# Sheet1.net
KiCad netlist of a schematic drawn in Altium Designer
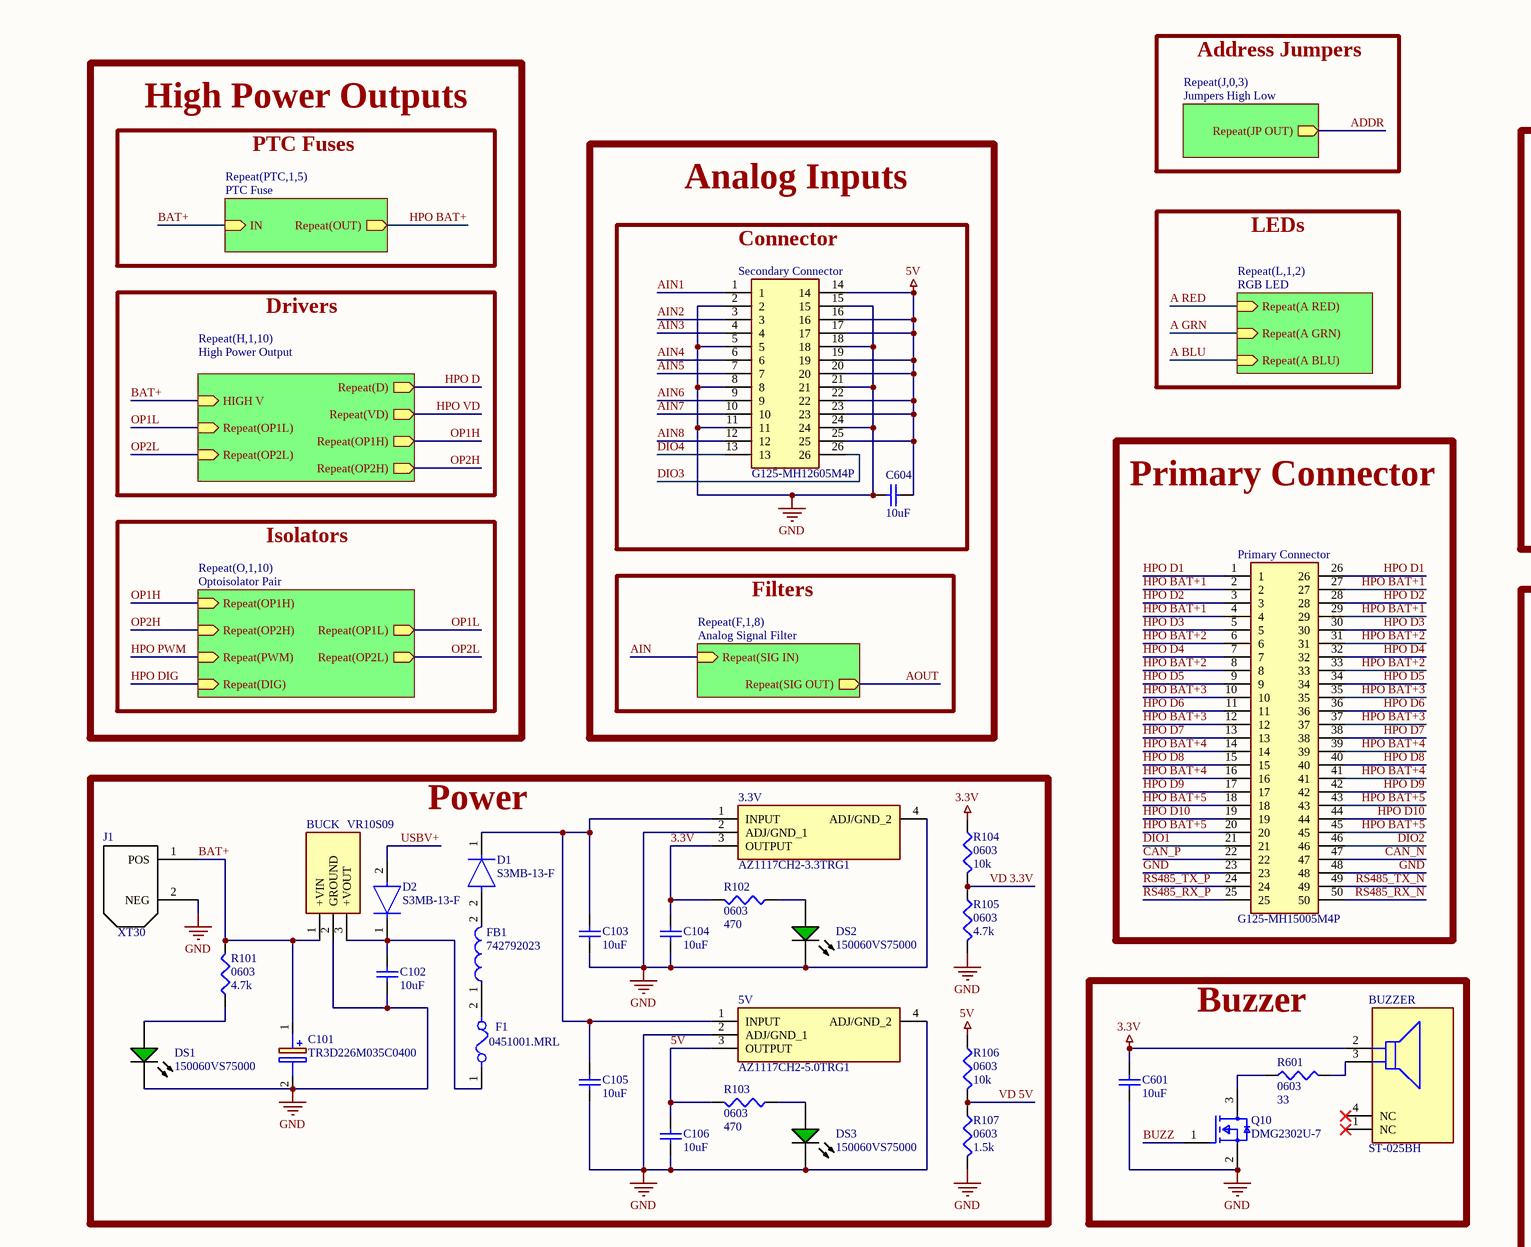
[diagram p0: Sheet1.SchDoc, top left]
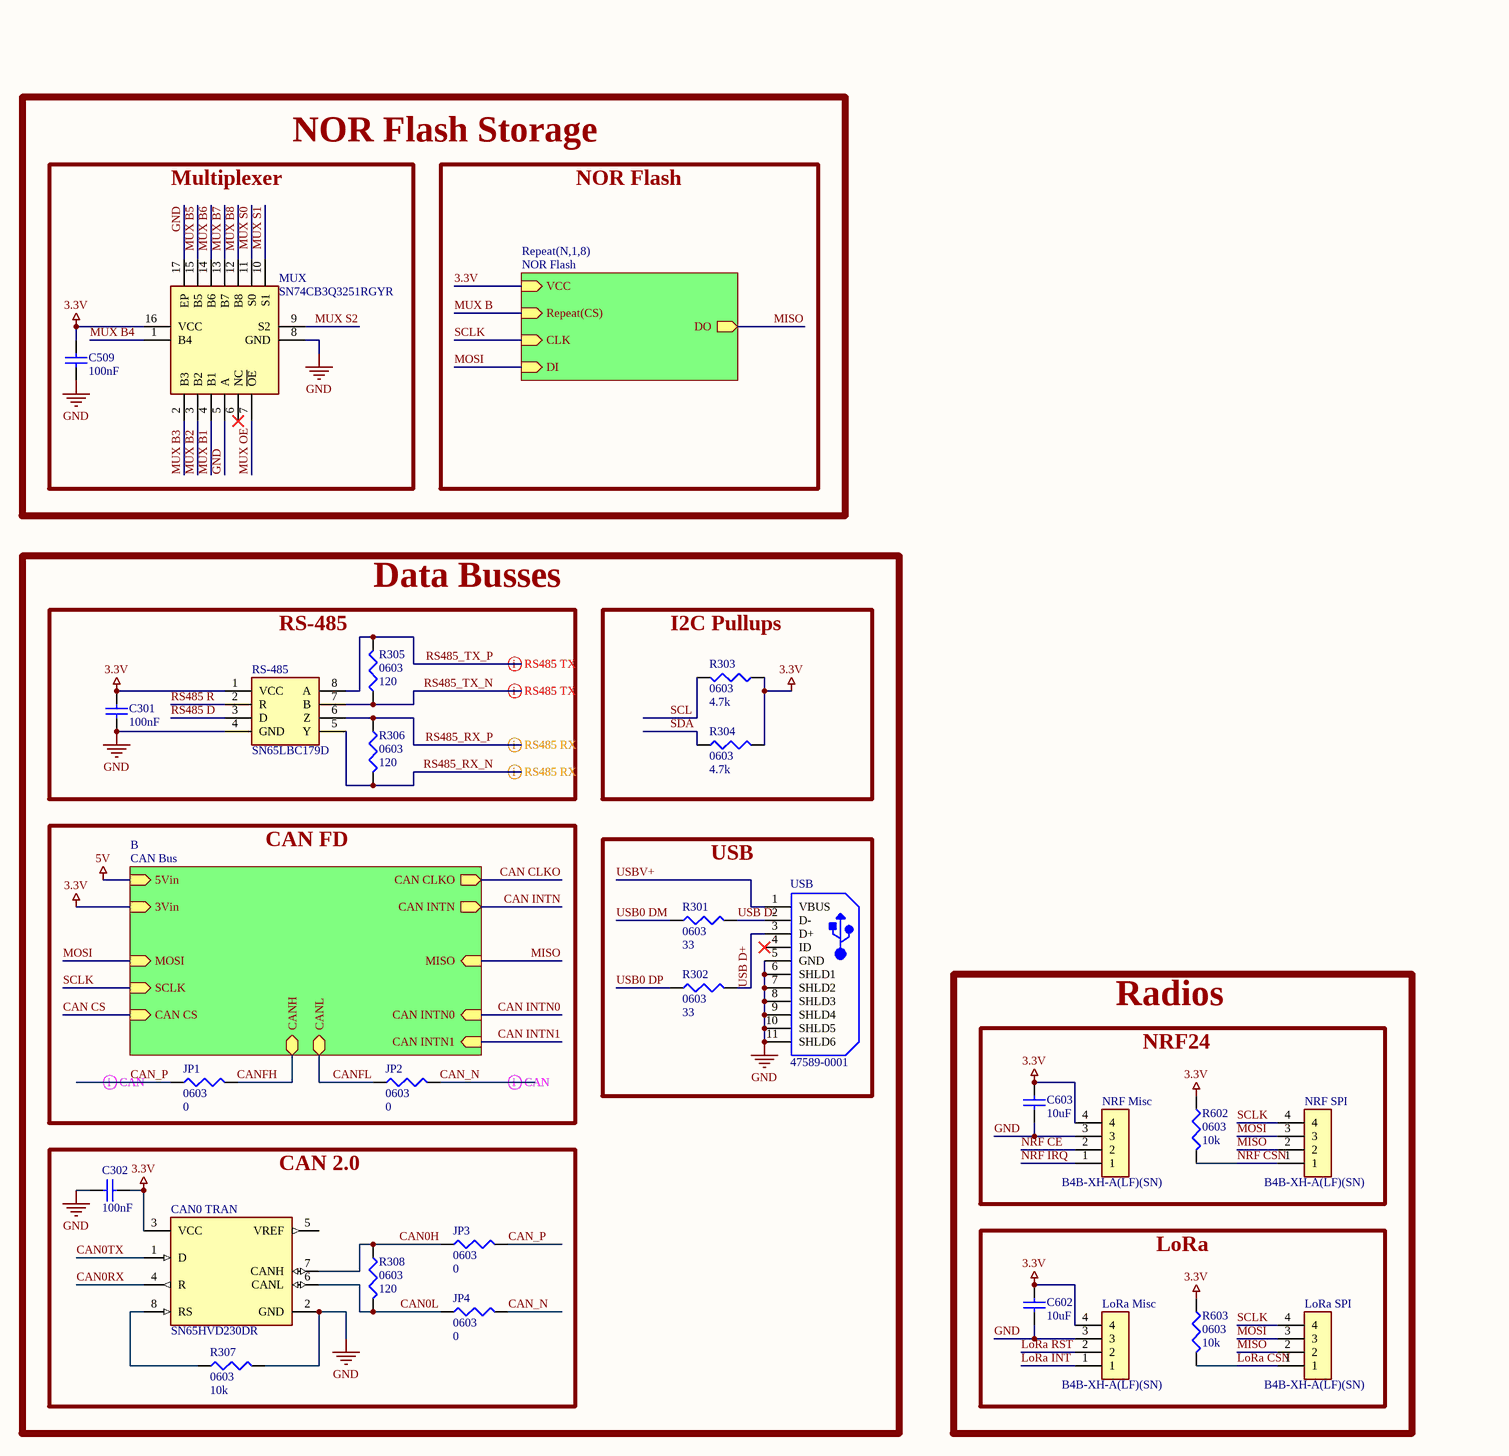
[diagram p1: Sheet1.SchDoc, top right]
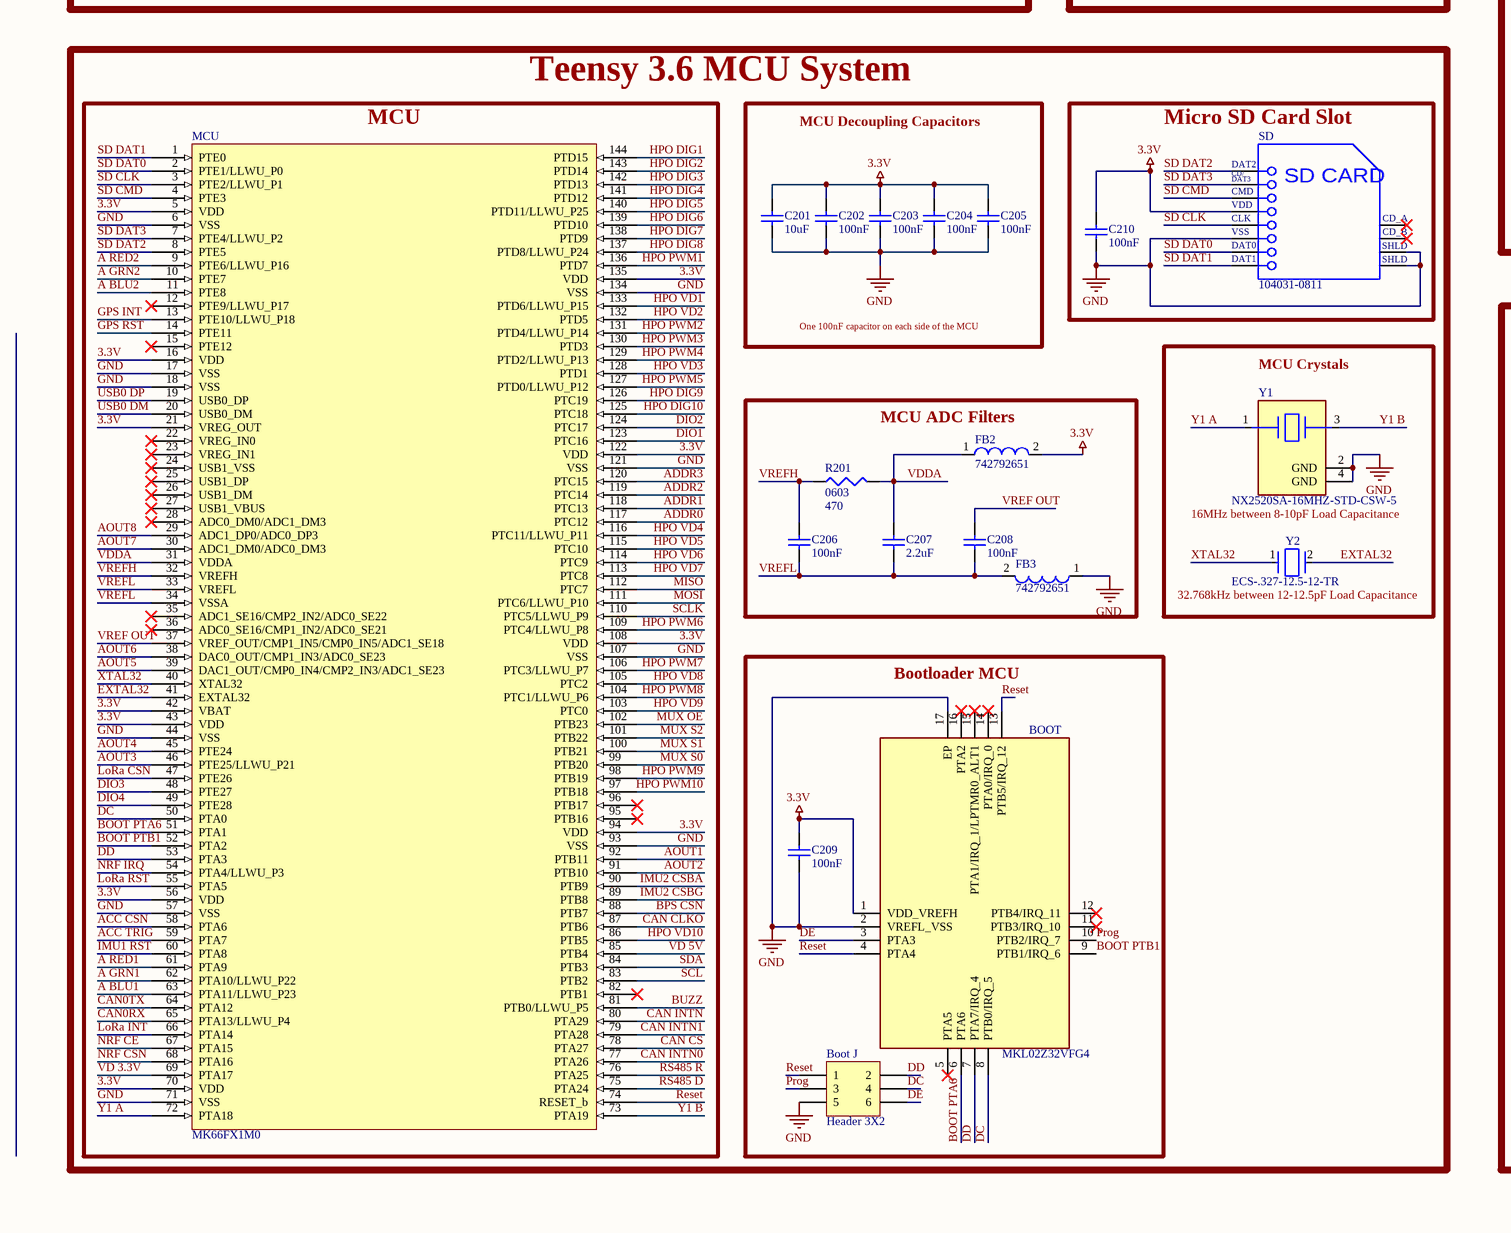
[diagram p2: Sheet1.SchDoc, bottom left]
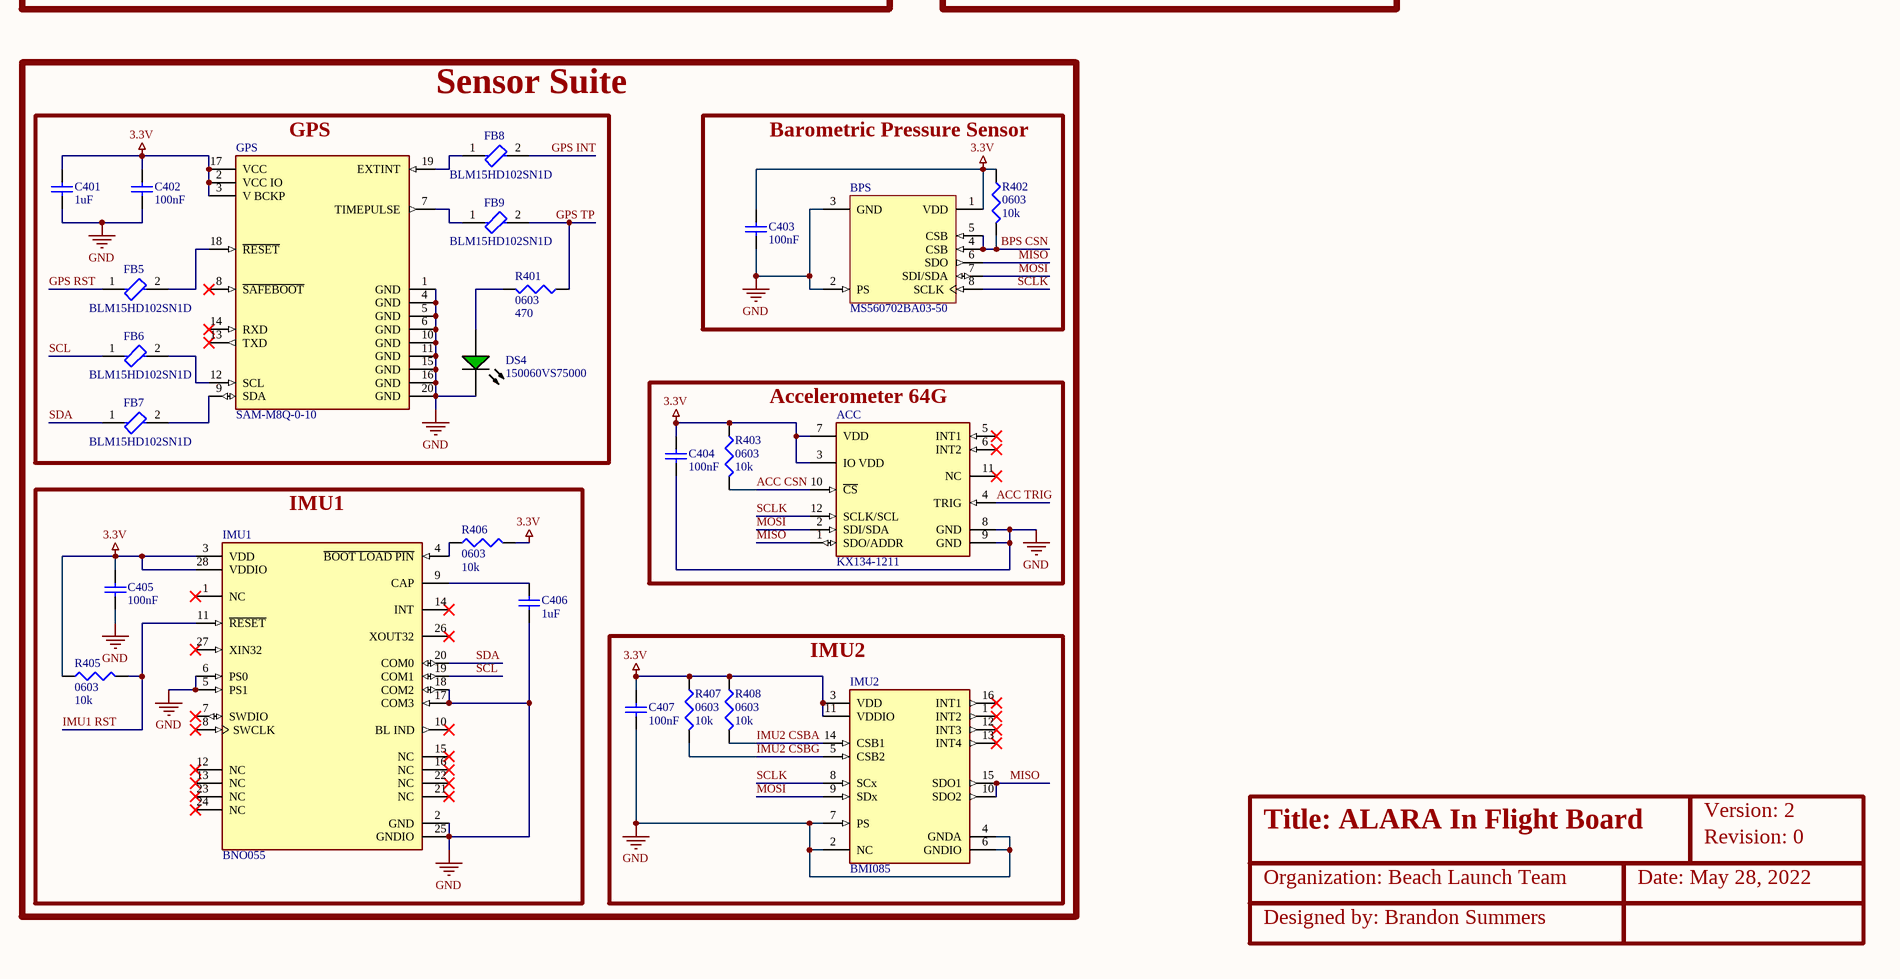
[diagram p3: Sheet1.SchDoc, bottom right]

(export (version "E")
  (design (tool "Eeschema 10.0.6"))
  (components
    (comp (ref "3.3V")
      (value "AZ1117CH2-3.3TRG1")
      (footprint "SamacSys:SOT230P700X180-4N")
      (description "Integrated Circuit")
      (libsource (lib "SamacSys") (part "AZ1117CH2-3.3TRG1"))
    )
    (comp (ref "5V")
      (value "AZ1117CH2-5.0TRG1")
      (footprint "SamacSys:SOT230P700X180-4N")
      (description "Integrated Circuit")
      (libsource (lib "SamacSys") (part "AZ1117CH2-5.0TRG1"))
    )
    (comp (ref "ACC")
      (value "KX134-1211")
      (footprint "FP-KX134-1211-MFG")
      (description "105C OPERATING HIGHER BANDWIDTH,")
      (libsource (lib "Altium Content Vault") (part "690d2a4d51cffb5fe50aad75ddab18e"))
    )
    (comp (ref "BOOT")
      (value "MKL02Z32VFG4")
      (footprint "SamacSys:QFN50P300X300X65-17N-D")
      (description "Integrated Circuit")
      (fields (field (name "MOUSER PART NUMBER") "841-MKL02Z32VFG4"))
      (libsource (lib "*") (part "MKL02Z32VFG4"))
    )
    (comp (ref "Boot J")
      (value "Header 3X2")
      (footprint "HDR2X3")
      (description "Header, 3-Pin, Dual row")
      (fields (field (name "PUBLISHER") "Altium Limited"))
      (libsource (lib "Miscellaneous Connectors") (part "Header 3X2"))
    )
    (comp (ref "BPS")
      (value "MS560702BA03-50")
      (footprint "TECO-MS560702BA03-50_V")
      (fields (field (name "MANUFACTURER") "TE Connectivity"))
      (libsource (lib "Altium Content Vault") (part "TECO-MS560702BA03-8"))
    )
    (comp (ref "BUCK")
      (value "VR10S09")
      (footprint "SamacSys:VR10S09")
      (description "Power Supply")
      (libsource (lib "SamacSys") (part "VR10S09"))
    )
    (comp (ref "BUZZER")
      (value "ST-025BH")
      (footprint "FP-ST-025BH-MFG")
      (description "AUDIO MAGNETIC XDCR 2-4V SMD")
      (fields
        (field (name "OCTOPART") "https://octopart.com/st-025bh-soberton-22171825")
        (field (name "MANUFACTURER") "Soberton Inc.")
      )
      (libsource (lib "Altium Content Vault") (part "31cc79d7b80ed2267c9b1676827f62c"))
    )
    (comp (ref "C101")
      (value "TR3D226M035C0400")
      (footprint "SamacSys:CAPPM7343X310N")
      (description "Capacitor Polarised")
      (libsource (lib "SamacSys") (part "TR3D226M035C0400"))
    )
    (comp (ref "C102")
      (value "10uF")
      (footprint "CAPC1608X95X40ML15T15")
      (fields (field (name "MANUFACTURER") "Vitramon") (field (name "PART NUMBER") "VJ0603Y104KXQCW1BC"))
      (libsource (lib "Altium Content Vault") (part "CAP"))
    )
    (comp (ref "C103")
      (value "10uF")
      (footprint "CAPC1608X95X40ML15T15")
      (fields (field (name "MANUFACTURER") "Vitramon") (field (name "PART NUMBER") "VJ0603Y104KXQCW1BC"))
      (libsource (lib "Altium Content Vault") (part "CAP"))
    )
    (comp (ref "C104")
      (value "10uF")
      (footprint "CAPC1608X95X40ML15T15")
      (fields (field (name "MANUFACTURER") "Vitramon") (field (name "PART NUMBER") "VJ0603Y104KXQCW1BC"))
      (libsource (lib "Altium Content Vault") (part "CAP"))
    )
    (comp (ref "C105")
      (value "10uF")
      (footprint "CAPC1608X95X40ML15T15")
      (fields (field (name "MANUFACTURER") "Vitramon") (field (name "PART NUMBER") "VJ0603Y104KXQCW1BC"))
      (libsource (lib "Altium Content Vault") (part "CAP"))
    )
    (comp (ref "C106")
      (value "10uF")
      (footprint "CAPC1608X95X40ML15T15")
      (fields (field (name "MANUFACTURER") "Vitramon") (field (name "PART NUMBER") "VJ0603Y104KXQCW1BC"))
      (libsource (lib "Altium Content Vault") (part "CAP"))
    )
    (comp (ref "C201")
      (value "10uF")
      (footprint "CAPC1608X95X40ML15T15")
      (fields (field (name "MANUFACTURER") "Vitramon") (field (name "PART NUMBER") "VJ0603Y104KXQCW1BC"))
      (libsource (lib "Altium Content Vault") (part "CAP"))
    )
    (comp (ref "C202")
      (value "100nF")
      (footprint "CAPC1608X95X40ML15T15")
      (fields (field (name "MANUFACTURER") "Vitramon") (field (name "PART NUMBER") "VJ0603Y104KXQCW1BC"))
      (libsource (lib "Altium Content Vault") (part "CAP"))
    )
    (comp (ref "C203")
      (value "100nF")
      (footprint "CAPC1608X95X40ML15T15")
      (fields (field (name "MANUFACTURER") "Vitramon") (field (name "PART NUMBER") "VJ0603Y104KXQCW1BC"))
      (libsource (lib "Altium Content Vault") (part "CAP"))
    )
    (comp (ref "C204")
      (value "100nF")
      (footprint "CAPC1608X95X40ML15T15")
      (fields (field (name "MANUFACTURER") "Vitramon") (field (name "PART NUMBER") "VJ0603Y104KXQCW1BC"))
      (libsource (lib "Altium Content Vault") (part "CAP"))
    )
    (comp (ref "C205")
      (value "100nF")
      (footprint "CAPC1608X95X40ML15T15")
      (fields (field (name "MANUFACTURER") "Vitramon") (field (name "PART NUMBER") "VJ0603Y104KXQCW1BC"))
      (libsource (lib "Altium Content Vault") (part "CAP"))
    )
    (comp (ref "C206")
      (value "100nF")
      (footprint "CAPC1608X95X40ML15T15")
      (fields (field (name "MANUFACTURER") "Vitramon") (field (name "PART NUMBER") "VJ0603Y104KXQCW1BC"))
      (libsource (lib "Altium Content Vault") (part "CAP"))
    )
    (comp (ref "C207")
      (value "2.2uF")
      (footprint "CAPC1608X95X40ML15T15")
      (fields (field (name "MANUFACTURER") "Vitramon") (field (name "PART NUMBER") "VJ0603Y104KXQCW1BC"))
      (libsource (lib "Altium Content Vault") (part "CAP"))
    )
    (comp (ref "C208")
      (value "100nF")
      (footprint "CAPC1608X95X40ML15T15")
      (fields (field (name "MANUFACTURER") "Vitramon") (field (name "PART NUMBER") "VJ0603Y104KXQCW1BC"))
      (libsource (lib "Altium Content Vault") (part "CAP"))
    )
    (comp (ref "C209")
      (value "100nF")
      (footprint "CAPC1608X95X40ML15T15")
      (fields (field (name "MANUFACTURER") "Vitramon") (field (name "PART NUMBER") "VJ0603Y104KXQCW1BC"))
      (libsource (lib "Altium Content Vault") (part "CAP"))
    )
    (comp (ref "C210")
      (value "100nF")
      (footprint "CAPC1608X95X40ML15T15")
      (fields (field (name "MANUFACTURER") "Vitramon") (field (name "PART NUMBER") "VJ0603Y104KXQCW1BC"))
      (libsource (lib "Altium Content Vault") (part "CAP"))
    )
    (comp (ref "C301")
      (value "100nF")
      (footprint "CAPC1608X95X40ML15T15")
      (fields (field (name "MANUFACTURER") "Vitramon") (field (name "PART NUMBER") "VJ0603Y104KXQCW1BC"))
      (libsource (lib "Altium Content Vault") (part "CAP"))
    )
    (comp (ref "C302")
      (value "100nF")
      (footprint "CAPC1608X95X40ML15T15")
      (fields (field (name "MANUFACTURER") "Vitramon") (field (name "PART NUMBER") "VJ0603Y104KXQCW1BC"))
      (libsource (lib "Altium Content Vault") (part "CAP"))
    )
    (comp (ref "C401")
      (value "1uF")
      (footprint "CAPC1608X95X40ML15T15")
      (fields (field (name "MANUFACTURER") "Vitramon") (field (name "PART NUMBER") "VJ0603Y104KXQCW1BC"))
      (libsource (lib "Altium Content Vault") (part "CAP"))
    )
    (comp (ref "C402")
      (value "100nF")
      (footprint "CAPC1608X95X40ML15T15")
      (fields (field (name "MANUFACTURER") "Vitramon") (field (name "PART NUMBER") "VJ0603Y104KXQCW1BC"))
      (libsource (lib "Altium Content Vault") (part "CAP"))
    )
    (comp (ref "C403")
      (value "100nF")
      (footprint "CAPC1608X95X40ML15T15")
      (fields (field (name "MANUFACTURER") "Vitramon") (field (name "PART NUMBER") "VJ0603Y104KXQCW1BC"))
      (libsource (lib "Altium Content Vault") (part "CAP"))
    )
    (comp (ref "C404")
      (value "100nF")
      (footprint "CAPC1608X95X40ML15T15")
      (fields (field (name "MANUFACTURER") "Vitramon") (field (name "PART NUMBER") "VJ0603Y104KXQCW1BC"))
      (libsource (lib "Altium Content Vault") (part "CAP"))
    )
    (comp (ref "C405")
      (value "100nF")
      (footprint "CAPC1608X95X40ML15T15")
      (fields (field (name "MANUFACTURER") "Vitramon") (field (name "PART NUMBER") "VJ0603Y104KXQCW1BC"))
      (libsource (lib "Altium Content Vault") (part "CAP"))
    )
    (comp (ref "C406")
      (value "1uF")
      (footprint "CAPC1608X95X40ML15T15")
      (fields (field (name "MANUFACTURER") "Vitramon") (field (name "PART NUMBER") "VJ0603Y104KXQCW1BC"))
      (libsource (lib "Altium Content Vault") (part "CAP"))
    )
    (comp (ref "C407")
      (value "100nF")
      (footprint "CAPC1608X95X40ML15T15")
      (fields (field (name "MANUFACTURER") "Vitramon") (field (name "PART NUMBER") "VJ0603Y104KXQCW1BC"))
      (libsource (lib "Altium Content Vault") (part "CAP"))
    )
    (comp (ref "C509")
      (value "100nF")
      (footprint "CAPC1608X95X40ML15T15")
      (fields (field (name "MANUFACTURER") "Vitramon") (field (name "PART NUMBER") "VJ0603Y104KXQCW1BC"))
      (libsource (lib "Altium Content Vault") (part "CAP"))
    )
    (comp (ref "C601")
      (value "10uF")
      (footprint "CAPC1608X95X40ML15T15")
      (fields (field (name "MANUFACTURER") "Vitramon") (field (name "PART NUMBER") "VJ0603Y104KXQCW1BC"))
      (libsource (lib "Altium Content Vault") (part "CAP"))
    )
    (comp (ref "C602")
      (value "10uF")
      (footprint "CAPC1608X95X40ML15T15")
      (fields (field (name "MANUFACTURER") "Vitramon") (field (name "PART NUMBER") "VJ0603Y104KXQCW1BC"))
      (libsource (lib "Altium Content Vault") (part "CAP"))
    )
    (comp (ref "C603")
      (value "10uF")
      (footprint "CAPC1608X95X40ML15T15")
      (fields (field (name "MANUFACTURER") "Vitramon") (field (name "PART NUMBER") "VJ0603Y104KXQCW1BC"))
      (libsource (lib "Altium Content Vault") (part "CAP"))
    )
    (comp (ref "C604")
      (value "10uF")
      (footprint "CAPC1608X95X40ML15T15")
      (fields (field (name "MANUFACTURER") "Vitramon") (field (name "PART NUMBER") "VJ0603Y104KXQCW1BC"))
      (libsource (lib "Altium Content Vault") (part "CAP"))
    )
    (comp (ref "CAN0 TRAN")
      (value "SN65HVD230DR")
      (footprint "FP-D0008A-IPC_A")
      (description "IC TRANSCEIVER HALF 1/1 8SOIC")
      (libsource (lib "Altium Content Vault") (part "43b56812b1adf0e60a7acfb7c27ab91"))
    )
    (comp (ref "D1")
      (value "S3MB-13-F")
      (footprint "FP-SMB-MFG")
      (description "DIODE GEN PURP 1KV 3A SMB")
      (fields
        (field (name "MANUFACTURER") "Diodes Inc.")
        (field (name "OCTOPART") "https://octopart.com/s3mb-13-f-diodes+inc.-333387")
      )
      (libsource (lib "Altium Content Vault") (part "d7152d700b627762746794eb795d46e"))
    )
    (comp (ref "D2")
      (value "S3MB-13-F")
      (footprint "FP-SMB-MFG")
      (description "DIODE GEN PURP 1KV 3A SMB")
      (fields
        (field (name "MANUFACTURER") "Diodes Inc.")
        (field (name "OCTOPART") "https://octopart.com/s3mb-13-f-diodes+inc.-333387")
      )
      (libsource (lib "Altium Content Vault") (part "d7152d700b627762746794eb795d46e"))
    )
    (comp (ref "DS1")
      (value "150060VS75000")
      (footprint "WE-150060VS75000_V")
      (libsource (lib "Altium Content Vault") (part "LED_GREEN_K1A2-2"))
    )
    (comp (ref "DS2")
      (value "150060VS75000")
      (footprint "WE-150060VS75000_V")
      (libsource (lib "Altium Content Vault") (part "LED_GREEN_K1A2-2"))
    )
    (comp (ref "DS3")
      (value "150060VS75000")
      (footprint "WE-150060VS75000_V")
      (libsource (lib "Altium Content Vault") (part "LED_GREEN_K1A2-2"))
    )
    (comp (ref "DS4")
      (value "150060VS75000")
      (footprint "WE-150060VS75000_V")
      (libsource (lib "Altium Content Vault") (part "LED_GREEN_K1A2-2"))
    )
    (comp (ref "F1")
      (value "0451001.MRL")
      (footprint "FP-0451-MFG")
      (description "FUSE BRD MNT 1A 125VAC/VDC 2SMD")
      (fields
        (field (name "OCTOPART") "https://octopart.com/0451001.mrl-littelfuse-566368")
        (field (name "MANUFACTURER") "Littelfuse Inc")
      )
      (libsource (lib "Altium Content Vault") (part "5bcf9b9f640e542cf0359d10258e979"))
    )
    (comp (ref "FB1")
      (value "742792023")
      (footprint "SMD-0805")
      (description "SMD EMI Suppression Ferrite Bead WE-CBF, Z = 120 Ohm")
      (libsource (lib "Altium Content Vault") (part "PAS-IND-INDUCTOR-2"))
    )
    (comp (ref "FB2")
      (value "742792651")
      (footprint "SMD-0603")
      (description "SMD EMI Suppression Ferrite Bead WE-CBF, Z = 600 Ohm")
      (libsource (lib "Altium Content Vault") (part "PAS-IND-INDUCTOR-2"))
    )
    (comp (ref "FB3")
      (value "742792651")
      (footprint "SMD-0603")
      (description "SMD EMI Suppression Ferrite Bead WE-CBF, Z = 600 Ohm")
      (libsource (lib "Altium Content Vault") (part "PAS-IND-INDUCTOR-2"))
    )
    (comp (ref "FB5")
      (value "BLM15HD102SN1D")
      (footprint "FP-BLM15-0_05-IPC_C")
      (description "Chip Ferrite Bead, 0402, 1000Ω @ 100MHz, 1.25Ω, 25%, 250mA")
      (fields (field (name "TOLERANCE") "25%"))
      (libsource (lib "Altium Content Vault") (part "5f30dd21d616792df468990f7003faa"))
    )
    (comp (ref "FB6")
      (value "BLM15HD102SN1D")
      (footprint "FP-BLM15-0_05-IPC_C")
      (description "Chip Ferrite Bead, 0402, 1000Ω @ 100MHz, 1.25Ω, 25%, 250mA")
      (fields (field (name "TOLERANCE") "25%"))
      (libsource (lib "Altium Content Vault") (part "5f30dd21d616792df468990f7003faa"))
    )
    (comp (ref "FB7")
      (value "BLM15HD102SN1D")
      (footprint "FP-BLM15-0_05-IPC_C")
      (description "Chip Ferrite Bead, 0402, 1000Ω @ 100MHz, 1.25Ω, 25%, 250mA")
      (fields (field (name "TOLERANCE") "25%"))
      (libsource (lib "Altium Content Vault") (part "5f30dd21d616792df468990f7003faa"))
    )
    (comp (ref "FB8")
      (value "BLM15HD102SN1D")
      (footprint "FP-BLM15-0_05-IPC_C")
      (description "Chip Ferrite Bead, 0402, 1000Ω @ 100MHz, 1.25Ω, 25%, 250mA")
      (fields (field (name "TOLERANCE") "25%"))
      (libsource (lib "Altium Content Vault") (part "5f30dd21d616792df468990f7003faa"))
    )
    (comp (ref "FB9")
      (value "BLM15HD102SN1D")
      (footprint "FP-BLM15-0_05-IPC_C")
      (description "Chip Ferrite Bead, 0402, 1000Ω @ 100MHz, 1.25Ω, 25%, 250mA")
      (fields (field (name "TOLERANCE") "25%"))
      (libsource (lib "Altium Content Vault") (part "5f30dd21d616792df468990f7003faa"))
    )
    (comp (ref "GPS")
      (value "SAM-M8Q-0-10")
      (footprint "FP-SAM-M8Q-0-10-MFG")
      (description "RF RX GALILEO 1.575GHZ/1.602GHZ")
      (fields
        (field (name "MANUFACTURER") "uBlox")
        (field (name "OCTOPART") "https://octopart.com/sam-m8q-0-10-u-blox-88247750")
      )
      (libsource (lib "Altium Content Vault") (part "e897669bc61729ed63f6e62e0b1e840"))
    )
    (comp (ref "IMU1")
      (value "BNO055")
      (footprint "FP-BNO055-MFG")
      (description "IMU ACCEL/GYRO/MAG I2C 28LGA")
      (libsource (lib "Altium Content Vault") (part "ba837af00a0b6167256f888b31462b1"))
    )
    (comp (ref "IMU2")
      (value "BMI085")
      (footprint "FP-BMI055-MFG")
      (description "IMU ACCEL/GYRO I2C/SPI 16LGA")
      (libsource (lib "Altium Content Vault") (part "27928433b13d6d742e94b461c0d61b2"))
    )
    (comp (ref "J1") (value "XT30") (footprint "XT30") (libsource (lib "XT30") (part "XT30")))
    (comp (ref "JP1")
      (value "0603")
      (footprint "J1-0603")
      (description "Resistor")
      (fields (field (name "ALTIUM_VALUE") "0") (field (name "PUBLISHER") "Altium Limited"))
      (libsource (lib "Miscellaneous Devices") (part "Res3"))
    )
    (comp (ref "JP2")
      (value "0603")
      (footprint "J1-0603")
      (description "Resistor")
      (fields (field (name "ALTIUM_VALUE") "0") (field (name "PUBLISHER") "Altium Limited"))
      (libsource (lib "Miscellaneous Devices") (part "Res3"))
    )
    (comp (ref "JP3")
      (value "0603")
      (footprint "J1-0603")
      (description "Resistor")
      (fields (field (name "ALTIUM_VALUE") "0") (field (name "PUBLISHER") "Altium Limited"))
      (libsource (lib "Miscellaneous Devices") (part "Res3"))
    )
    (comp (ref "JP4")
      (value "0603")
      (footprint "J1-0603")
      (description "Resistor")
      (fields (field (name "ALTIUM_VALUE") "0") (field (name "PUBLISHER") "Altium Limited"))
      (libsource (lib "Miscellaneous Devices") (part "Res3"))
    )
    (comp (ref "LoRa Misc")
      (value "B4B-XH-A(LF)(SN)")
      (footprint "JST_B4B-XH-A(LF)(SN)")
      (description "XH Series 4 Position 2.5 mm Pitch Through Hole Crimp Top Entry Shrouded Header")
      (fields (field (name "MF") "{'manufacturer': u'JST Sales America Inc.'}"))
      (libsource (lib "SnapEDA_Library") (part "B4B-XH-A(LF)(SN)"))
    )
    (comp (ref "LoRa SPI")
      (value "B4B-XH-A(LF)(SN)")
      (footprint "JST_B4B-XH-A(LF)(SN)")
      (description "XH Series 4 Position 2.5 mm Pitch Through Hole Crimp Top Entry Shrouded Header")
      (fields (field (name "MF") "{'manufacturer': u'JST Sales America Inc.'}"))
      (libsource (lib "SnapEDA_Library") (part "B4B-XH-A(LF)(SN)"))
    )
    (comp (ref "MCU")
      (value "MK66FX1M0")
      (footprint "LQFP144 0.5mm Pitch")
      (libsource (lib "MK66FX1M0VLQ18") (part "COMPONENT_1"))
    )
    (comp (ref "MUX")
      (value "SN74CB3Q3251RGYR")
      (footprint "SamacSys:SN74CBT3257CRGYR")
      (description "Integrated Circuit")
      (libsource (lib "*") (part "SN74CB3Q3251RGYR"))
    )
    (comp (ref "NRF Misc")
      (value "B4B-XH-A(LF)(SN)")
      (footprint "JST_B4B-XH-A(LF)(SN)")
      (description "XH Series 4 Position 2.5 mm Pitch Through Hole Crimp Top Entry Shrouded Header")
      (fields (field (name "MF") "{'manufacturer': u'JST Sales America Inc.'}"))
      (libsource (lib "SnapEDA_Library") (part "B4B-XH-A(LF)(SN)"))
    )
    (comp (ref "NRF SPI")
      (value "B4B-XH-A(LF)(SN)")
      (footprint "JST_B4B-XH-A(LF)(SN)")
      (description "XH Series 4 Position 2.5 mm Pitch Through Hole Crimp Top Entry Shrouded Header")
      (fields (field (name "MF") "{'manufacturer': u'JST Sales America Inc.'}"))
      (libsource (lib "SnapEDA_Library") (part "B4B-XH-A(LF)(SN)"))
    )
    (comp (ref "Primary Connector")
      (value "G125-MH15005M4P")
      (footprint "SamacSys:G125-MH15005M4P")
      (description "Connector")
      (fields (field (name "MOUSER PART NUMBER") "855-G125MH1505M4PM4P"))
      (libsource (lib "SamacSys") (part "G125-MH15005M4P"))
    )
    (comp (ref "Q10")
      (value "DMG2302U-7")
      (footprint "FP-SOT23-MFG")
      (description "MOSFET N-CH 20V 4.2A SOT23")
      (libsource (lib "Altium Content Vault") (part "381a366367e4312d0f7d2747150cb42"))
    )
    (comp (ref "R101")
      (value "0603")
      (footprint "J1-0603")
      (description "Resistor")
      (fields (field (name "ALTIUM_VALUE") "4.7k") (field (name "PUBLISHER") "Altium Limited"))
      (libsource (lib "Miscellaneous Devices") (part "Res3"))
    )
    (comp (ref "R102")
      (value "0603")
      (footprint "J1-0603")
      (description "Resistor")
      (fields (field (name "ALTIUM_VALUE") "470") (field (name "PUBLISHER") "Altium Limited"))
      (libsource (lib "Miscellaneous Devices") (part "Res3"))
    )
    (comp (ref "R103")
      (value "0603")
      (footprint "J1-0603")
      (description "Resistor")
      (fields (field (name "ALTIUM_VALUE") "470") (field (name "PUBLISHER") "Altium Limited"))
      (libsource (lib "Miscellaneous Devices") (part "Res3"))
    )
    (comp (ref "R104")
      (value "0603")
      (footprint "J1-0603")
      (description "Resistor")
      (fields (field (name "ALTIUM_VALUE") "10k") (field (name "PUBLISHER") "Altium Limited"))
      (libsource (lib "Miscellaneous Devices") (part "Res3"))
    )
    (comp (ref "R105")
      (value "0603")
      (footprint "J1-0603")
      (description "Resistor")
      (fields (field (name "ALTIUM_VALUE") "4.7k") (field (name "PUBLISHER") "Altium Limited"))
      (libsource (lib "Miscellaneous Devices") (part "Res3"))
    )
    (comp (ref "R106")
      (value "0603")
      (footprint "J1-0603")
      (description "Resistor")
      (fields (field (name "ALTIUM_VALUE") "10k") (field (name "PUBLISHER") "Altium Limited"))
      (libsource (lib "Miscellaneous Devices") (part "Res3"))
    )
    (comp (ref "R107")
      (value "0603")
      (footprint "J1-0603")
      (description "Resistor")
      (fields (field (name "ALTIUM_VALUE") "1.5k") (field (name "PUBLISHER") "Altium Limited"))
      (libsource (lib "Miscellaneous Devices") (part "Res3"))
    )
    (comp (ref "R201")
      (value "0603")
      (footprint "J1-0603")
      (description "Resistor")
      (fields (field (name "ALTIUM_VALUE") "470") (field (name "PUBLISHER") "Altium Limited"))
      (libsource (lib "Miscellaneous Devices") (part "Res3"))
    )
    (comp (ref "R301")
      (value "0603")
      (footprint "J1-0603")
      (description "Resistor")
      (fields (field (name "ALTIUM_VALUE") "33") (field (name "PUBLISHER") "Altium Limited"))
      (libsource (lib "Miscellaneous Devices") (part "Res3"))
    )
    (comp (ref "R302")
      (value "0603")
      (footprint "J1-0603")
      (description "Resistor")
      (fields (field (name "ALTIUM_VALUE") "33") (field (name "PUBLISHER") "Altium Limited"))
      (libsource (lib "Miscellaneous Devices") (part "Res3"))
    )
    (comp (ref "R303")
      (value "0603")
      (footprint "J1-0603")
      (description "Resistor")
      (fields (field (name "ALTIUM_VALUE") "4.7k") (field (name "PUBLISHER") "Altium Limited"))
      (libsource (lib "Miscellaneous Devices") (part "Res3"))
    )
    (comp (ref "R304")
      (value "0603")
      (footprint "J1-0603")
      (description "Resistor")
      (fields (field (name "ALTIUM_VALUE") "4.7k") (field (name "PUBLISHER") "Altium Limited"))
      (libsource (lib "Miscellaneous Devices") (part "Res3"))
    )
    (comp (ref "R305")
      (value "0603")
      (footprint "J1-0603")
      (description "Resistor")
      (fields (field (name "ALTIUM_VALUE") "120") (field (name "PUBLISHER") "Altium Limited"))
      (libsource (lib "Miscellaneous Devices") (part "Res3"))
    )
    (comp (ref "R306")
      (value "0603")
      (footprint "J1-0603")
      (description "Resistor")
      (fields (field (name "ALTIUM_VALUE") "120") (field (name "PUBLISHER") "Altium Limited"))
      (libsource (lib "Miscellaneous Devices") (part "Res3"))
    )
    (comp (ref "R307")
      (value "0603")
      (footprint "J1-0603")
      (description "Resistor")
      (fields (field (name "ALTIUM_VALUE") "10k") (field (name "PUBLISHER") "Altium Limited"))
      (libsource (lib "Miscellaneous Devices") (part "Res3"))
    )
    (comp (ref "R308")
      (value "0603")
      (footprint "J1-0603")
      (description "Resistor")
      (fields (field (name "ALTIUM_VALUE") "120") (field (name "PUBLISHER") "Altium Limited"))
      (libsource (lib "Miscellaneous Devices") (part "Res3"))
    )
    (comp (ref "R401")
      (value "0603")
      (footprint "J1-0603")
      (description "Resistor")
      (fields (field (name "ALTIUM_VALUE") "470") (field (name "PUBLISHER") "Altium Limited"))
      (libsource (lib "Miscellaneous Devices") (part "Res3"))
    )
    (comp (ref "R402")
      (value "0603")
      (footprint "J1-0603")
      (description "Resistor")
      (fields (field (name "ALTIUM_VALUE") "10k") (field (name "PUBLISHER") "Altium Limited"))
      (libsource (lib "Miscellaneous Devices") (part "Res3"))
    )
    (comp (ref "R403")
      (value "0603")
      (footprint "J1-0603")
      (description "Resistor")
      (fields (field (name "ALTIUM_VALUE") "10k") (field (name "PUBLISHER") "Altium Limited"))
      (libsource (lib "Miscellaneous Devices") (part "Res3"))
    )
    (comp (ref "R405")
      (value "0603")
      (footprint "J1-0603")
      (description "Resistor")
      (fields (field (name "ALTIUM_VALUE") "10k") (field (name "PUBLISHER") "Altium Limited"))
      (libsource (lib "Miscellaneous Devices") (part "Res3"))
    )
    (comp (ref "R406")
      (value "0603")
      (footprint "J1-0603")
      (description "Resistor")
      (fields (field (name "ALTIUM_VALUE") "10k") (field (name "PUBLISHER") "Altium Limited"))
      (libsource (lib "Miscellaneous Devices") (part "Res3"))
    )
    (comp (ref "R407")
      (value "0603")
      (footprint "J1-0603")
      (description "Resistor")
      (fields (field (name "ALTIUM_VALUE") "10k") (field (name "PUBLISHER") "Altium Limited"))
      (libsource (lib "Miscellaneous Devices") (part "Res3"))
    )
    (comp (ref "R408")
      (value "0603")
      (footprint "J1-0603")
      (description "Resistor")
      (fields (field (name "ALTIUM_VALUE") "10k") (field (name "PUBLISHER") "Altium Limited"))
      (libsource (lib "Miscellaneous Devices") (part "Res3"))
    )
    (comp (ref "R601")
      (value "0603")
      (footprint "J1-0603")
      (description "Resistor")
      (fields (field (name "ALTIUM_VALUE") "33") (field (name "PUBLISHER") "Altium Limited"))
      (libsource (lib "Miscellaneous Devices") (part "Res3"))
    )
    (comp (ref "R602")
      (value "0603")
      (footprint "J1-0603")
      (description "Resistor")
      (fields (field (name "ALTIUM_VALUE") "10k") (field (name "PUBLISHER") "Altium Limited"))
      (libsource (lib "Miscellaneous Devices") (part "Res3"))
    )
    (comp (ref "R603")
      (value "0603")
      (footprint "J1-0603")
      (description "Resistor")
      (fields (field (name "ALTIUM_VALUE") "10k") (field (name "PUBLISHER") "Altium Limited"))
      (libsource (lib "Miscellaneous Devices") (part "Res3"))
    )
    (comp (ref "RS-485")
      (value "SN65LBC179D")
      (footprint "SamacSys:SOIC127P600X175-8N")
      (description "Integrated Circuit")
      (libsource (lib "*") (part "SN65LBC179D"))
    )
    (comp (ref "SD")
      (value "104031-0811")
      (footprint "MOLX-104031-0811_V")
      (description "Micro SD Card, RA, -25 to 85 degC, 8-Pin SMD, RoHS, Tape and Reel")
      (fields (field (name "MANUFACTURER") "Molex"))
      (libsource (lib "Altium Content Vault") (part "CN-SD-8-2SW-2S"))
    )
    (comp (ref "Secondary Connector")
      (value "G125-MH12605M4P")
      (footprint "SamacSys:G125-MH12605M4P")
      (description "Connector")
      (fields (field (name "MOUSER PART NUMBER") "855-G125MH1265M4PM4P"))
      (libsource (lib "SamacSys") (part "G125-MH12605M4P"))
    )
    (comp (ref "USB")
      (value "47589-0001")
      (footprint "MOLX-47589-0001_V")
      (description "Right Angle Female Type AB Micro USB Connector, 30 V, 1.8 A, -30 to 85 degC, RoHS, Tape and Reel")
      (fields (field (name "MANUFACTURER") "Molex"))
      (libsource (lib "Altium Content Vault") (part "USB-5-6SHLD"))
    )
    (comp (ref "Y1")
      (value "NX2520SA-16MHZ-STD-CSW-5")
      (footprint "FP-NX2520SA-MFG")
      (description "CRYSTAL 16.0000MHZ 8PF SMD")
      (libsource (lib "Altium Content Vault") (part "07cd68334262f73c450eeb7a763f26b"))
    )
    (comp (ref "Y2")
      (value "ECS-.327-12.5-12-TR")
      (footprint "FP-ECX-12-MFG")
      (description "CRYSTAL 32.7680KHZ 12.5PF SMD")
      (fields (field (name "TOLERANCE") "20ppm"))
      (libsource (lib "Altium Content Vault") (part "99724985039315a44fd0d1401b84e49"))
    )
  )
  (nets
    (net (code "2") (name "/A BLU1") (class "Default")
      (node (ref "MCU") (pin "63") (pinfunction "PTA11/LLWU_P23_63") (pintype "input"))
    )
    (net (code "3") (name "/A BLU2") (class "Default")
      (node (ref "MCU") (pin "11") (pinfunction "PTE8_11") (pintype "input"))
    )
    (net (code "5") (name "/A GRN1") (class "Default")
      (node (ref "MCU") (pin "62") (pinfunction "PTA10/LLWU_P22_62") (pintype "input"))
    )
    (net (code "6") (name "/A GRN2") (class "Default")
      (node (ref "MCU") (pin "10") (pinfunction "PTE7_10") (pintype "input"))
    )
    (net (code "8") (name "/A RED1") (class "Default")
      (node (ref "MCU") (pin "61") (pinfunction "PTA9_61") (pintype "input"))
    )
    (net (code "9") (name "/A RED2") (class "Default")
      (node (ref "MCU") (pin "9") (pinfunction "PTE6/LLWU_P16_9") (pintype "input"))
    )
    (net (code "10") (name "/ACC CSN") (class "Default")
      (node (ref "ACC") (pin "10") (pinfunction "~{CS}_10") (pintype "input"))
      (node (ref "MCU") (pin "58") (pinfunction "PTA6_58") (pintype "input"))
      (node (ref "R403") (pin "2") (pinfunction "2_2") (pintype "passive"))
    )
    (net (code "11") (name "/ACC TRIG") (class "Default")
      (node (ref "ACC") (pin "4") (pinfunction "TRIG_4") (pintype "input"))
      (node (ref "MCU") (pin "59") (pinfunction "PTA7_59") (pintype "input"))
    )
    (net (code "13") (name "/ADDR0") (class "Default")
      (node (ref "MCU") (pin "117") (pinfunction "PTC12_117") (pintype "input"))
    )
    (net (code "14") (name "/ADDR1") (class "Default")
      (node (ref "MCU") (pin "118") (pinfunction "PTC13_118") (pintype "input"))
    )
    (net (code "15") (name "/ADDR2") (class "Default")
      (node (ref "MCU") (pin "119") (pinfunction "PTC14_119") (pintype "input"))
    )
    (net (code "16") (name "/ADDR3") (class "Default")
      (node (ref "MCU") (pin "120") (pinfunction "PTC15_120") (pintype "input"))
    )
    (net (code "18") (name "/AIN1") (class "Default")
      (node (ref "Secondary Connector") (pin "1") (pinfunction "1_1") (pintype "passive"))
    )
    (net (code "19") (name "/AIN2") (class "Default")
      (node (ref "Secondary Connector") (pin "3") (pinfunction "3_3") (pintype "passive"))
    )
    (net (code "20") (name "/AIN3") (class "Default")
      (node (ref "Secondary Connector") (pin "4") (pinfunction "4_4") (pintype "passive"))
    )
    (net (code "21") (name "/AIN4") (class "Default")
      (node (ref "Secondary Connector") (pin "6") (pinfunction "6_6") (pintype "passive"))
    )
    (net (code "22") (name "/AIN5") (class "Default")
      (node (ref "Secondary Connector") (pin "7") (pinfunction "7_7") (pintype "passive"))
    )
    (net (code "23") (name "/AIN6") (class "Default")
      (node (ref "Secondary Connector") (pin "9") (pinfunction "9_9") (pintype "passive"))
    )
    (net (code "24") (name "/AIN7") (class "Default")
      (node (ref "Secondary Connector") (pin "10") (pinfunction "10_10") (pintype "passive"))
    )
    (net (code "25") (name "/AIN8") (class "Default")
      (node (ref "Secondary Connector") (pin "12") (pinfunction "12_12") (pintype "passive"))
    )
    (net (code "27") (name "/AOUT1") (class "Default")
      (node (ref "MCU") (pin "92") (pinfunction "PTB11_92") (pintype "input"))
    )
    (net (code "28") (name "/AOUT2") (class "Default")
      (node (ref "MCU") (pin "91") (pinfunction "PTB10_91") (pintype "input"))
    )
    (net (code "29") (name "/AOUT3") (class "Default")
      (node (ref "MCU") (pin "46") (pinfunction "PTE25/LLWU_P21_46") (pintype "input"))
    )
    (net (code "30") (name "/AOUT4") (class "Default")
      (node (ref "MCU") (pin "45") (pinfunction "PTE24_45") (pintype "input"))
    )
    (net (code "31") (name "/AOUT5") (class "Default")
      (node (ref "MCU") (pin "39") (pinfunction "DAC1_OUT/CMP0_IN4/CMP2_IN3/ADC1_SE23_39") (pintype "input"))
    )
    (net (code "32") (name "/AOUT6") (class "Default")
      (node (ref "MCU") (pin "38") (pinfunction "DAC0_OUT/CMP1_IN3/ADC0_SE23_38") (pintype "input"))
    )
    (net (code "33") (name "/AOUT7") (class "Default")
      (node (ref "MCU") (pin "30") (pinfunction "ADC1_DM0/ADC0_DM3_30") (pintype "input"))
    )
    (net (code "34") (name "/AOUT8") (class "Default")
      (node (ref "MCU") (pin "29") (pinfunction "ADC1_DP0/ADC0_DP3_29") (pintype "input"))
    )
    (net (code "35") (name "/BAT+") (class "Default")
      (node (ref "BUCK") (pin "1") (pinfunction "+VIN_1") (pintype "passive"))
      (node (ref "C101") (pin "1") (pinfunction "+_1") (pintype "passive"))
      (node (ref "J1") (pin "1") (pinfunction "POS_1") (pintype "passive"))
      (node (ref "R101") (pin "2") (pinfunction "2_2") (pintype "passive"))
    )
    (net (code "36") (name "/BOOT PTA6") (class "Default")
      (node (ref "BOOT") (pin "6") (pinfunction "PTA6_6") (pintype "passive"))
      (node (ref "MCU") (pin "51") (pinfunction "PTA1_51") (pintype "input"))
    )
    (net (code "37") (name "/BOOT PTB1") (class "Default")
      (node (ref "BOOT") (pin "9") (pinfunction "PTB1/IRQ_6_9") (pintype "passive"))
      (node (ref "MCU") (pin "52") (pinfunction "PTA2_52") (pintype "input"))
    )
    (net (code "38") (name "/BPS CSN") (class "Default")
      (node (ref "BPS") (pin "4") (pinfunction "CSB_4") (pintype "input"))
      (node (ref "BPS") (pin "5") (pinfunction "CSB_5") (pintype "input"))
      (node (ref "MCU") (pin "88") (pinfunction "PTB7_88") (pintype "input"))
      (node (ref "R402") (pin "2") (pinfunction "2_2") (pintype "passive"))
    )
    (net (code "39") (name "/BUZZ") (class "Default")
      (node (ref "MCU") (pin "81") (pinfunction "PTB0/LLWU_P5_81") (pintype "input"))
      (node (ref "Q10") (pin "1") (pinfunction "G_1") (pintype "passive"))
    )
    (net (code "40") (name "/CAN CLKO") (class "Default")
      (node (ref "MCU") (pin "87") (pinfunction "PTB6_87") (pintype "input"))
    )
    (net (code "41") (name "/CAN CS") (class "Default")
      (node (ref "MCU") (pin "78") (pinfunction "PTA27_78") (pintype "input"))
    )
    (net (code "42") (name "/CAN INTN") (class "Default")
      (node (ref "MCU") (pin "80") (pinfunction "PTA29_80") (pintype "input"))
    )
    (net (code "43") (name "/CAN INTN0") (class "Default")
      (node (ref "MCU") (pin "77") (pinfunction "PTA26_77") (pintype "input"))
    )
    (net (code "44") (name "/CAN INTN1") (class "Default")
      (node (ref "MCU") (pin "79") (pinfunction "PTA28_79") (pintype "input"))
    )
    (net (code "45") (name "/CAN0H") (class "Default")
      (node (ref "CAN0 TRAN") (pin "7") (pinfunction "CANH_7") (pintype "bidirectional"))
      (node (ref "JP3") (pin "1") (pinfunction "1_1") (pintype "passive"))
      (node (ref "R308") (pin "1") (pinfunction "1_1") (pintype "passive"))
    )
    (net (code "46") (name "/CAN0L") (class "Default")
      (node (ref "CAN0 TRAN") (pin "6") (pinfunction "CANL_6") (pintype "bidirectional"))
      (node (ref "JP4") (pin "1") (pinfunction "1_1") (pintype "passive"))
      (node (ref "R308") (pin "2") (pinfunction "2_2") (pintype "passive"))
    )
    (net (code "47") (name "/CAN0RX") (class "Default")
      (node (ref "CAN0 TRAN") (pin "4") (pinfunction "R_4") (pintype "output"))
      (node (ref "MCU") (pin "65") (pinfunction "PTA13/LLWU_P4_65") (pintype "input"))
    )
    (net (code "48") (name "/CAN0TX") (class "Default")
      (node (ref "CAN0 TRAN") (pin "1") (pinfunction "D_1") (pintype "input"))
      (node (ref "MCU") (pin "64") (pinfunction "PTA12_64") (pintype "input"))
    )
    (net (code "49") (name "/CANFH") (class "Default")
      (node (ref "JP1") (pin "2") (pinfunction "2_2") (pintype "passive"))
    )
    (net (code "50") (name "/CANFL") (class "Default")
      (node (ref "JP2") (pin "1") (pinfunction "1_1") (pintype "passive"))
    )
    (net (code "51") (name "/CAN_N") (class "Default")
      (node (ref "JP2") (pin "2") (pinfunction "2_2") (pintype "passive"))
      (node (ref "JP4") (pin "2") (pinfunction "2_2") (pintype "passive"))
      (node (ref "Primary Connector") (pin "47") (pinfunction "47_47") (pintype "passive"))
    )
    (net (code "52") (name "/CAN_P") (class "Default")
      (node (ref "JP1") (pin "1") (pinfunction "1_1") (pintype "passive"))
      (node (ref "JP3") (pin "2") (pinfunction "2_2") (pintype "passive"))
      (node (ref "Primary Connector") (pin "22") (pinfunction "22_22") (pintype "passive"))
    )
    (net (code "53") (name "/DC") (class "Default")
      (node (ref "BOOT") (pin "8") (pinfunction "PTB0/IRQ_5_8") (pintype "passive"))
      (node (ref "Boot J") (pin "4") (pinfunction "4_4") (pintype "passive"))
      (node (ref "MCU") (pin "50") (pinfunction "PTA0_50") (pintype "input"))
    )
    (net (code "54") (name "/DD") (class "Default")
      (node (ref "BOOT") (pin "7") (pinfunction "PTA7/IRQ_4_7") (pintype "passive"))
      (node (ref "Boot J") (pin "2") (pinfunction "2_2") (pintype "passive"))
      (node (ref "MCU") (pin "53") (pinfunction "PTA3_53") (pintype "input"))
    )
    (net (code "55") (name "/DE") (class "Default")
      (node (ref "BOOT") (pin "3") (pinfunction "PTA3_3") (pintype "passive"))
      (node (ref "Boot J") (pin "6") (pinfunction "6_6") (pintype "passive"))
    )
    (net (code "56") (name "/DIO1") (class "Default")
      (node (ref "MCU") (pin "123") (pinfunction "PTC16_123") (pintype "input"))
      (node (ref "Primary Connector") (pin "21") (pinfunction "21_21") (pintype "passive"))
    )
    (net (code "57") (name "/DIO2") (class "Default")
      (node (ref "MCU") (pin "124") (pinfunction "PTC17_124") (pintype "input"))
      (node (ref "Primary Connector") (pin "46") (pinfunction "46_46") (pintype "passive"))
    )
    (net (code "58") (name "/DIO3") (class "Default")
      (node (ref "MCU") (pin "48") (pinfunction "PTE27_48") (pintype "input"))
      (node (ref "Secondary Connector") (pin "26") (pinfunction "26_26") (pintype "passive"))
    )
    (net (code "59") (name "/DIO4") (class "Default")
      (node (ref "MCU") (pin "49") (pinfunction "PTE28_49") (pintype "input"))
      (node (ref "Secondary Connector") (pin "13") (pinfunction "13_13") (pintype "passive"))
    )
    (net (code "60") (name "/EXTAL32") (class "Default")
      (node (ref "MCU") (pin "41") (pinfunction "EXTAL32_41") (pintype "input"))
      (node (ref "Y2") (pin "2") (pinfunction "Out/In_2") (pintype "passive"))
    )
    (net (code "61") (name "/GPS INT") (class "Default")
      (node (ref "FB8") (pin "2") (pinfunction "2_2") (pintype "passive"))
      (node (ref "MCU") (pin "13") (pinfunction "PTE10/LLWU_P18_13") (pintype "input"))
    )
    (net (code "62") (name "/GPS RST") (class "Default")
      (node (ref "FB5") (pin "1") (pinfunction "1_1") (pintype "passive"))
      (node (ref "MCU") (pin "14") (pinfunction "PTE11_14") (pintype "input"))
    )
    (net (code "63") (name "/GPS TP") (class "Default")
      (node (ref "FB9") (pin "2") (pinfunction "2_2") (pintype "passive"))
      (node (ref "R401") (pin "1") (pinfunction "1_1") (pintype "passive"))
    )
    (net (code "65") (name "/HPO BAT+1") (class "Default")
      (node (ref "Primary Connector") (pin "2") (pinfunction "2_2") (pintype "passive"))
      (node (ref "Primary Connector") (pin "27") (pinfunction "27_27") (pintype "passive"))
      (node (ref "Primary Connector") (pin "29") (pinfunction "29_29") (pintype "passive"))
      (node (ref "Primary Connector") (pin "4") (pinfunction "4_4") (pintype "passive"))
    )
    (net (code "66") (name "/HPO BAT+2") (class "Default")
      (node (ref "Primary Connector") (pin "31") (pinfunction "31_31") (pintype "passive"))
      (node (ref "Primary Connector") (pin "33") (pinfunction "33_33") (pintype "passive"))
      (node (ref "Primary Connector") (pin "6") (pinfunction "6_6") (pintype "passive"))
      (node (ref "Primary Connector") (pin "8") (pinfunction "8_8") (pintype "passive"))
    )
    (net (code "67") (name "/HPO BAT+3") (class "Default")
      (node (ref "Primary Connector") (pin "10") (pinfunction "10_10") (pintype "passive"))
      (node (ref "Primary Connector") (pin "12") (pinfunction "12_12") (pintype "passive"))
      (node (ref "Primary Connector") (pin "35") (pinfunction "35_35") (pintype "passive"))
      (node (ref "Primary Connector") (pin "37") (pinfunction "37_37") (pintype "passive"))
    )
    (net (code "68") (name "/HPO BAT+4") (class "Default")
      (node (ref "Primary Connector") (pin "14") (pinfunction "14_14") (pintype "passive"))
      (node (ref "Primary Connector") (pin "16") (pinfunction "16_16") (pintype "passive"))
      (node (ref "Primary Connector") (pin "39") (pinfunction "39_39") (pintype "passive"))
      (node (ref "Primary Connector") (pin "41") (pinfunction "41_41") (pintype "passive"))
    )
    (net (code "69") (name "/HPO BAT+5") (class "Default")
      (node (ref "Primary Connector") (pin "18") (pinfunction "18_18") (pintype "passive"))
      (node (ref "Primary Connector") (pin "20") (pinfunction "20_20") (pintype "passive"))
      (node (ref "Primary Connector") (pin "43") (pinfunction "43_43") (pintype "passive"))
      (node (ref "Primary Connector") (pin "45") (pinfunction "45_45") (pintype "passive"))
    )
    (net (code "71") (name "/HPO D1") (class "Default")
      (node (ref "Primary Connector") (pin "1") (pinfunction "1_1") (pintype "passive"))
      (node (ref "Primary Connector") (pin "26") (pinfunction "26_26") (pintype "passive"))
    )
    (net (code "72") (name "/HPO D2") (class "Default")
      (node (ref "Primary Connector") (pin "28") (pinfunction "28_28") (pintype "passive"))
      (node (ref "Primary Connector") (pin "3") (pinfunction "3_3") (pintype "passive"))
    )
    (net (code "73") (name "/HPO D3") (class "Default")
      (node (ref "Primary Connector") (pin "30") (pinfunction "30_30") (pintype "passive"))
      (node (ref "Primary Connector") (pin "5") (pinfunction "5_5") (pintype "passive"))
    )
    (net (code "74") (name "/HPO D4") (class "Default")
      (node (ref "Primary Connector") (pin "32") (pinfunction "32_32") (pintype "passive"))
      (node (ref "Primary Connector") (pin "7") (pinfunction "7_7") (pintype "passive"))
    )
    (net (code "75") (name "/HPO D5") (class "Default")
      (node (ref "Primary Connector") (pin "34") (pinfunction "34_34") (pintype "passive"))
      (node (ref "Primary Connector") (pin "9") (pinfunction "9_9") (pintype "passive"))
    )
    (net (code "76") (name "/HPO D6") (class "Default")
      (node (ref "Primary Connector") (pin "11") (pinfunction "11_11") (pintype "passive"))
      (node (ref "Primary Connector") (pin "36") (pinfunction "36_36") (pintype "passive"))
    )
    (net (code "77") (name "/HPO D7") (class "Default")
      (node (ref "Primary Connector") (pin "13") (pinfunction "13_13") (pintype "passive"))
      (node (ref "Primary Connector") (pin "38") (pinfunction "38_38") (pintype "passive"))
    )
    (net (code "78") (name "/HPO D8") (class "Default")
      (node (ref "Primary Connector") (pin "15") (pinfunction "15_15") (pintype "passive"))
      (node (ref "Primary Connector") (pin "40") (pinfunction "40_40") (pintype "passive"))
    )
    (net (code "79") (name "/HPO D9") (class "Default")
      (node (ref "Primary Connector") (pin "17") (pinfunction "17_17") (pintype "passive"))
      (node (ref "Primary Connector") (pin "42") (pinfunction "42_42") (pintype "passive"))
    )
    (net (code "80") (name "/HPO D10") (class "Default")
      (node (ref "Primary Connector") (pin "19") (pinfunction "19_19") (pintype "passive"))
      (node (ref "Primary Connector") (pin "44") (pinfunction "44_44") (pintype "passive"))
    )
    (net (code "82") (name "/HPO DIG1") (class "Default")
      (node (ref "MCU") (pin "144") (pinfunction "PTD15_144") (pintype "input"))
    )
    (net (code "83") (name "/HPO DIG2") (class "Default")
      (node (ref "MCU") (pin "143") (pinfunction "PTD14_143") (pintype "input"))
    )
    (net (code "84") (name "/HPO DIG3") (class "Default")
      (node (ref "MCU") (pin "142") (pinfunction "PTD13_142") (pintype "input"))
    )
    (net (code "85") (name "/HPO DIG4") (class "Default")
      (node (ref "MCU") (pin "141") (pinfunction "PTD12_141") (pintype "input"))
    )
    (net (code "86") (name "/HPO DIG5") (class "Default")
      (node (ref "MCU") (pin "140") (pinfunction "PTD11/LLWU_P25_140") (pintype "input"))
    )
    (net (code "87") (name "/HPO DIG6") (class "Default")
      (node (ref "MCU") (pin "139") (pinfunction "PTD10_139") (pintype "input"))
    )
    (net (code "88") (name "/HPO DIG7") (class "Default")
      (node (ref "MCU") (pin "138") (pinfunction "PTD9_138") (pintype "input"))
    )
    (net (code "89") (name "/HPO DIG8") (class "Default")
      (node (ref "MCU") (pin "137") (pinfunction "PTD8/LLWU_P24_137") (pintype "input"))
    )
    (net (code "90") (name "/HPO DIG9") (class "Default")
      (node (ref "MCU") (pin "126") (pinfunction "PTC19_126") (pintype "input"))
    )
    (net (code "91") (name "/HPO DIG10") (class "Default")
      (node (ref "MCU") (pin "125") (pinfunction "PTC18_125") (pintype "input"))
    )
    (net (code "93") (name "/HPO PWM1") (class "Default")
      (node (ref "MCU") (pin "136") (pinfunction "PTD7_136") (pintype "input"))
    )
    (net (code "94") (name "/HPO PWM2") (class "Default")
      (node (ref "MCU") (pin "131") (pinfunction "PTD4/LLWU_P14_131") (pintype "input"))
    )
    (net (code "95") (name "/HPO PWM3") (class "Default")
      (node (ref "MCU") (pin "130") (pinfunction "PTD3_130") (pintype "input"))
    )
    (net (code "96") (name "/HPO PWM4") (class "Default")
      (node (ref "MCU") (pin "129") (pinfunction "PTD2/LLWU_P13_129") (pintype "input"))
    )
    (net (code "97") (name "/HPO PWM5") (class "Default")
      (node (ref "MCU") (pin "127") (pinfunction "PTD0/LLWU_P12_127") (pintype "input"))
    )
    (net (code "98") (name "/HPO PWM6") (class "Default")
      (node (ref "MCU") (pin "109") (pinfunction "PTC4/LLWU_P8_109") (pintype "input"))
    )
    (net (code "99") (name "/HPO PWM7") (class "Default")
      (node (ref "MCU") (pin "106") (pinfunction "PTC3/LLWU_P7_106") (pintype "input"))
    )
    (net (code "100") (name "/HPO PWM8") (class "Default")
      (node (ref "MCU") (pin "104") (pinfunction "PTC1/LLWU_P6_104") (pintype "input"))
    )
    (net (code "101") (name "/HPO PWM9") (class "Default")
      (node (ref "MCU") (pin "98") (pinfunction "PTB19_98") (pintype "input"))
    )
    (net (code "102") (name "/HPO PWM10") (class "Default")
      (node (ref "MCU") (pin "97") (pinfunction "PTB18_97") (pintype "input"))
    )
    (net (code "104") (name "/HPO VD1") (class "Default")
      (node (ref "MCU") (pin "133") (pinfunction "PTD6/LLWU_P15_133") (pintype "input"))
    )
    (net (code "105") (name "/HPO VD2") (class "Default")
      (node (ref "MCU") (pin "132") (pinfunction "PTD5_132") (pintype "input"))
    )
    (net (code "106") (name "/HPO VD3") (class "Default")
      (node (ref "MCU") (pin "128") (pinfunction "PTD1_128") (pintype "input"))
    )
    (net (code "107") (name "/HPO VD4") (class "Default")
      (node (ref "MCU") (pin "116") (pinfunction "PTC11/LLWU_P11_116") (pintype "input"))
    )
    (net (code "108") (name "/HPO VD5") (class "Default")
      (node (ref "MCU") (pin "115") (pinfunction "PTC10_115") (pintype "input"))
    )
    (net (code "109") (name "/HPO VD6") (class "Default")
      (node (ref "MCU") (pin "114") (pinfunction "PTC9_114") (pintype "input"))
    )
    (net (code "110") (name "/HPO VD7") (class "Default")
      (node (ref "MCU") (pin "113") (pinfunction "PTC8_113") (pintype "input"))
    )
    (net (code "111") (name "/HPO VD8") (class "Default")
      (node (ref "MCU") (pin "105") (pinfunction "PTC2_105") (pintype "input"))
    )
    (net (code "112") (name "/HPO VD9") (class "Default")
      (node (ref "MCU") (pin "103") (pinfunction "PTC0_103") (pintype "input"))
    )
    (net (code "113") (name "/HPO VD10") (class "Default")
      (node (ref "MCU") (pin "86") (pinfunction "PTB5_86") (pintype "input"))
    )
    (net (code "114") (name "/IMU1 RST") (class "Default")
      (node (ref "IMU1") (pin "11") (pinfunction "~{RESET}_11") (pintype "input"))
      (node (ref "MCU") (pin "60") (pinfunction "PTA8_60") (pintype "input"))
      (node (ref "R405") (pin "2") (pinfunction "2_2") (pintype "passive"))
    )
    (net (code "115") (name "/IMU2 CSBA") (class "Default")
      (node (ref "IMU2") (pin "14") (pinfunction "CSB1_14") (pintype "input"))
      (node (ref "MCU") (pin "90") (pinfunction "PTB9_90") (pintype "input"))
      (node (ref "R408") (pin "2") (pinfunction "2_2") (pintype "passive"))
    )
    (net (code "116") (name "/IMU2 CSBG") (class "Default")
      (node (ref "IMU2") (pin "5") (pinfunction "CSB2_5") (pintype "input"))
      (node (ref "MCU") (pin "89") (pinfunction "PTB8_89") (pintype "input"))
      (node (ref "R407") (pin "2") (pinfunction "2_2") (pintype "passive"))
    )
    (net (code "117") (name "/LoRa CSN") (class "Default")
      (node (ref "LoRa SPI") (pin "1") (pinfunction "1_1") (pintype "passive"))
      (node (ref "MCU") (pin "47") (pinfunction "PTE26_47") (pintype "input"))
      (node (ref "R603") (pin "2") (pinfunction "2_2") (pintype "passive"))
    )
    (net (code "118") (name "/LoRa INT") (class "Default")
      (node (ref "LoRa Misc") (pin "1") (pinfunction "1_1") (pintype "passive"))
      (node (ref "MCU") (pin "66") (pinfunction "PTA14_66") (pintype "input"))
    )
    (net (code "119") (name "/LoRa RST") (class "Default")
      (node (ref "LoRa Misc") (pin "2") (pinfunction "2_2") (pintype "passive"))
      (node (ref "MCU") (pin "55") (pinfunction "PTA5_55") (pintype "input"))
    )
    (net (code "120") (name "/MISO") (class "Default")
      (node (ref "ACC") (pin "1") (pinfunction "SDO/ADDR_1") (pintype "bidirectional"))
      (node (ref "BPS") (pin "6") (pinfunction "SDO_6") (pintype "output"))
      (node (ref "IMU2") (pin "10") (pinfunction "SDO2_10") (pintype "output"))
      (node (ref "IMU2") (pin "15") (pinfunction "SDO1_15") (pintype "output"))
      (node (ref "LoRa SPI") (pin "2") (pinfunction "2_2") (pintype "passive"))
      (node (ref "MCU") (pin "112") (pinfunction "PTC7_112") (pintype "input"))
      (node (ref "NRF SPI") (pin "2") (pinfunction "2_2") (pintype "passive"))
    )
    (net (code "121") (name "/MOSI") (class "Default")
      (node (ref "ACC") (pin "2") (pinfunction "SDI/SDA_2") (pintype "input"))
      (node (ref "BPS") (pin "7") (pinfunction "SDI/SDA_7") (pintype "bidirectional"))
      (node (ref "IMU2") (pin "9") (pinfunction "SDx_9") (pintype "input"))
      (node (ref "LoRa SPI") (pin "3") (pinfunction "3_3") (pintype "passive"))
      (node (ref "MCU") (pin "111") (pinfunction "PTC6/LLWU_P10_111") (pintype "input"))
      (node (ref "NRF SPI") (pin "3") (pinfunction "3_3") (pintype "passive"))
    )
    (net (code "123") (name "/MUX B1") (class "Default")
      (node (ref "MUX") (pin "4") (pinfunction "B1_4") (pintype "passive"))
    )
    (net (code "124") (name "/MUX B2") (class "Default")
      (node (ref "MUX") (pin "3") (pinfunction "B2_3") (pintype "passive"))
    )
    (net (code "125") (name "/MUX B3") (class "Default")
      (node (ref "MUX") (pin "2") (pinfunction "B3_2") (pintype "passive"))
    )
    (net (code "126") (name "/MUX B4") (class "Default")
      (node (ref "MUX") (pin "1") (pinfunction "B4_1") (pintype "passive"))
    )
    (net (code "127") (name "/MUX B5") (class "Default")
      (node (ref "MUX") (pin "15") (pinfunction "B5_15") (pintype "passive"))
    )
    (net (code "128") (name "/MUX B6") (class "Default")
      (node (ref "MUX") (pin "14") (pinfunction "B6_14") (pintype "passive"))
    )
    (net (code "129") (name "/MUX B7") (class "Default")
      (node (ref "MUX") (pin "13") (pinfunction "B7_13") (pintype "passive"))
    )
    (net (code "130") (name "/MUX B8") (class "Default")
      (node (ref "MUX") (pin "12") (pinfunction "B8_12") (pintype "passive"))
    )
    (net (code "131") (name "/MUX OE") (class "Default")
      (node (ref "MCU") (pin "102") (pinfunction "PTB23_102") (pintype "input"))
      (node (ref "MUX") (pin "7") (pinfunction "~{OE}_7") (pintype "passive"))
    )
    (net (code "132") (name "/MUX S0") (class "Default")
      (node (ref "MCU") (pin "99") (pinfunction "PTB20_99") (pintype "input"))
      (node (ref "MUX") (pin "11") (pinfunction "S0_11") (pintype "passive"))
    )
    (net (code "133") (name "/MUX S1") (class "Default")
      (node (ref "MCU") (pin "100") (pinfunction "PTB21_100") (pintype "input"))
      (node (ref "MUX") (pin "10") (pinfunction "S1_10") (pintype "passive"))
    )
    (net (code "134") (name "/MUX S2") (class "Default")
      (node (ref "MCU") (pin "101") (pinfunction "PTB22_101") (pintype "input"))
      (node (ref "MUX") (pin "9") (pinfunction "S2_9") (pintype "passive"))
    )
    (net (code "135") (name "/NRF CE") (class "Default")
      (node (ref "MCU") (pin "67") (pinfunction "PTA15_67") (pintype "input"))
      (node (ref "NRF Misc") (pin "2") (pinfunction "2_2") (pintype "passive"))
    )
    (net (code "136") (name "/NRF CSN") (class "Default")
      (node (ref "MCU") (pin "68") (pinfunction "PTA16_68") (pintype "input"))
      (node (ref "NRF SPI") (pin "1") (pinfunction "1_1") (pintype "passive"))
      (node (ref "R602") (pin "2") (pinfunction "2_2") (pintype "passive"))
    )
    (net (code "137") (name "/NRF IRQ") (class "Default")
      (node (ref "MCU") (pin "54") (pinfunction "PTA4/LLWU_P3_54") (pintype "input"))
      (node (ref "NRF Misc") (pin "1") (pinfunction "1_1") (pintype "passive"))
    )
    (net (code "142") (name "/Prog") (class "Default")
      (node (ref "BOOT") (pin "10") (pinfunction "PTB2/IRQ_7_10") (pintype "passive"))
      (node (ref "Boot J") (pin "3") (pinfunction "3_3") (pintype "passive"))
    )
    (net (code "143") (name "/RS485 D") (class "Default")
      (node (ref "MCU") (pin "75") (pinfunction "PTA24_75") (pintype "input"))
      (node (ref "RS-485") (pin "3") (pinfunction "D_3") (pintype "passive"))
    )
    (net (code "144") (name "/RS485 R") (class "Default")
      (node (ref "MCU") (pin "76") (pinfunction "PTA25_76") (pintype "input"))
      (node (ref "RS-485") (pin "2") (pinfunction "R_2") (pintype "passive"))
    )
    (net (code "145") (name "/RS485_RX_N") (class "Default")
      (node (ref "Primary Connector") (pin "50") (pinfunction "50_50") (pintype "passive"))
      (node (ref "R306") (pin "2") (pinfunction "2_2") (pintype "passive"))
      (node (ref "RS-485") (pin "5") (pinfunction "Y_5") (pintype "passive"))
    )
    (net (code "146") (name "/RS485_RX_P") (class "Default")
      (node (ref "Primary Connector") (pin "25") (pinfunction "25_25") (pintype "passive"))
      (node (ref "R306") (pin "1") (pinfunction "1_1") (pintype "passive"))
      (node (ref "RS-485") (pin "6") (pinfunction "Z_6") (pintype "passive"))
    )
    (net (code "147") (name "/RS485_TX_N") (class "Default")
      (node (ref "Primary Connector") (pin "49") (pinfunction "49_49") (pintype "passive"))
      (node (ref "R305") (pin "1") (pinfunction "1_1") (pintype "passive"))
      (node (ref "RS-485") (pin "7") (pinfunction "B_7") (pintype "passive"))
    )
    (net (code "148") (name "/RS485_TX_P") (class "Default")
      (node (ref "Primary Connector") (pin "24") (pinfunction "24_24") (pintype "passive"))
      (node (ref "R305") (pin "2") (pinfunction "2_2") (pintype "passive"))
      (node (ref "RS-485") (pin "8") (pinfunction "A_8") (pintype "passive"))
    )
    (net (code "149") (name "/Reset") (class "Default")
      (node (ref "BOOT") (pin "13") (pinfunction "PTB5/IRQ_12_13") (pintype "passive"))
      (node (ref "BOOT") (pin "4") (pinfunction "PTA4_4") (pintype "passive"))
      (node (ref "Boot J") (pin "1") (pinfunction "1_1") (pintype "passive"))
      (node (ref "MCU") (pin "74") (pinfunction "RESET_b_74") (pintype "input"))
    )
    (net (code "150") (name "/SCL") (class "Default")
      (node (ref "FB6") (pin "1") (pinfunction "1_1") (pintype "passive"))
      (node (ref "IMU1") (pin "19") (pinfunction "COM1_19") (pintype "bidirectional"))
      (node (ref "MCU") (pin "83") (pinfunction "PTB2_83") (pintype "input"))
      (node (ref "R303") (pin "2") (pinfunction "2_2") (pintype "passive"))
    )
    (net (code "151") (name "/SCLK") (class "Default")
      (node (ref "ACC") (pin "12") (pinfunction "SCLK/SCL_12") (pintype "input"))
      (node (ref "BPS") (pin "8") (pinfunction "SCLK_8") (pintype "input"))
      (node (ref "IMU2") (pin "8") (pinfunction "SCx_8") (pintype "input"))
      (node (ref "LoRa SPI") (pin "4") (pinfunction "4_4") (pintype "passive"))
      (node (ref "MCU") (pin "110") (pinfunction "PTC5/LLWU_P9_110") (pintype "input"))
      (node (ref "NRF SPI") (pin "4") (pinfunction "4_4") (pintype "passive"))
    )
    (net (code "152") (name "/SD CLK") (class "Default")
      (node (ref "MCU") (pin "3") (pinfunction "PTE2/LLWU_P1_3") (pintype "input"))
      (node (ref "SD") (pin "5") (pinfunction "CLK_5") (pintype "passive"))
    )
    (net (code "153") (name "/SD CMD") (class "Default")
      (node (ref "MCU") (pin "4") (pinfunction "PTE3_4") (pintype "input"))
      (node (ref "SD") (pin "3") (pinfunction "VSS1_3") (pintype "passive"))
    )
    (net (code "154") (name "/SD DAT0") (class "Default")
      (node (ref "MCU") (pin "2") (pinfunction "PTE1/LLWU_P0_2") (pintype "input"))
      (node (ref "SD") (pin "7") (pinfunction "DAT0_7") (pintype "passive"))
    )
    (net (code "155") (name "/SD DAT1") (class "Default")
      (node (ref "MCU") (pin "1") (pinfunction "PTE0_1") (pintype "input"))
      (node (ref "SD") (pin "8") (pinfunction "DAT1_8") (pintype "passive"))
    )
    (net (code "156") (name "/SD DAT2") (class "Default")
      (node (ref "MCU") (pin "8") (pinfunction "PTE5_8") (pintype "input"))
      (node (ref "SD") (pin "1") (pinfunction "CD/DAT3_1") (pintype "passive"))
    )
    (net (code "157") (name "/SD DAT3") (class "Default")
      (node (ref "MCU") (pin "7") (pinfunction "PTE4/LLWU_P2_7") (pintype "input"))
      (node (ref "SD") (pin "2") (pinfunction "CMD_2") (pintype "passive"))
    )
    (net (code "158") (name "/SDA") (class "Default")
      (node (ref "FB7") (pin "1") (pinfunction "1_1") (pintype "passive"))
      (node (ref "IMU1") (pin "20") (pinfunction "COM0_20") (pintype "bidirectional"))
      (node (ref "MCU") (pin "84") (pinfunction "PTB3_84") (pintype "input"))
      (node (ref "R304") (pin "1") (pinfunction "1_1") (pintype "passive"))
    )
    (net (code "159") (name "/USB D+") (class "Default")
      (node (ref "R302") (pin "2") (pinfunction "2_2") (pintype "passive"))
      (node (ref "USB") (pin "3") (pinfunction "D+_3") (pintype "passive"))
    )
    (net (code "160") (name "/USB D-") (class "Default")
      (node (ref "R301") (pin "2") (pinfunction "2_2") (pintype "passive"))
      (node (ref "USB") (pin "2") (pinfunction "D-_2") (pintype "passive"))
    )
    (net (code "161") (name "/USB0 DM") (class "Default")
      (node (ref "MCU") (pin "20") (pinfunction "USB0_DM_20") (pintype "input"))
      (node (ref "R301") (pin "1") (pinfunction "1_1") (pintype "passive"))
    )
    (net (code "162") (name "/USB0 DP") (class "Default")
      (node (ref "MCU") (pin "19") (pinfunction "USB0_DP_19") (pintype "input"))
      (node (ref "R302") (pin "1") (pinfunction "1_1") (pintype "passive"))
    )
    (net (code "163") (name "/USBV+") (class "Default")
      (node (ref "D2") (pin "2") (pinfunction "A_2") (pintype "passive"))
      (node (ref "USB") (pin "1") (pinfunction "VBUS_1") (pintype "passive"))
    )
    (net (code "164") (name "/VD 3.3V") (class "Default")
      (node (ref "MCU") (pin "69") (pinfunction "PTA17_69") (pintype "input"))
      (node (ref "R104") (pin "2") (pinfunction "2_2") (pintype "passive"))
      (node (ref "R105") (pin "1") (pinfunction "1_1") (pintype "passive"))
    )
    (net (code "165") (name "/VD 5V") (class "Default")
      (node (ref "MCU") (pin "85") (pinfunction "PTB4_85") (pintype "input"))
      (node (ref "R106") (pin "2") (pinfunction "2_2") (pintype "passive"))
      (node (ref "R107") (pin "1") (pinfunction "1_1") (pintype "passive"))
    )
    (net (code "166") (name "/VDDA") (class "Default")
      (node (ref "C207") (pin "2") (pinfunction "2_2") (pintype "passive"))
      (node (ref "FB2") (pin "1") (pinfunction "1_1") (pintype "passive"))
      (node (ref "MCU") (pin "31") (pinfunction "VDDA_31") (pintype "input"))
      (node (ref "R201") (pin "2") (pinfunction "2_2") (pintype "passive"))
    )
    (net (code "167") (name "/VREF OUT") (class "Default")
      (node (ref "C208") (pin "2") (pinfunction "2_2") (pintype "passive"))
      (node (ref "MCU") (pin "37") (pinfunction "VREF_OUT/CMP1_IN5/CMP0_IN5/ADC1_SE18_37") (pintype "input"))
    )
    (net (code "168") (name "/VREFH") (class "Default")
      (node (ref "C206") (pin "2") (pinfunction "2_2") (pintype "passive"))
      (node (ref "MCU") (pin "32") (pinfunction "VREFH_32") (pintype "input"))
      (node (ref "R201") (pin "1") (pinfunction "1_1") (pintype "passive"))
    )
    (net (code "169") (name "/VREFL") (class "Default")
      (node (ref "C206") (pin "1") (pinfunction "1_1") (pintype "passive"))
      (node (ref "C207") (pin "1") (pinfunction "1_1") (pintype "passive"))
      (node (ref "C208") (pin "1") (pinfunction "1_1") (pintype "passive"))
      (node (ref "FB3") (pin "2") (pinfunction "2_2") (pintype "passive"))
      (node (ref "MCU") (pin "33") (pinfunction "VREFL_33") (pintype "input"))
      (node (ref "MCU") (pin "34") (pinfunction "VSSA_34") (pintype "input"))
    )
    (net (code "170") (name "/XTAL32") (class "Default")
      (node (ref "MCU") (pin "40") (pinfunction "XTAL32_40") (pintype "input"))
      (node (ref "Y2") (pin "1") (pinfunction "In/Out_1") (pintype "passive"))
    )
    (net (code "171") (name "/Y1 A") (class "Default")
      (node (ref "MCU") (pin "72") (pinfunction "PTA18_72") (pintype "input"))
      (node (ref "Y1") (pin "1") (pinfunction "1_1") (pintype "passive"))
    )
    (net (code "172") (name "/Y1 B") (class "Default")
      (node (ref "MCU") (pin "73") (pinfunction "PTA19_73") (pintype "input"))
      (node (ref "Y1") (pin "3") (pinfunction "3_3") (pintype "passive"))
    )
    (net (code "173") (name "3.3V") (class "Default")
      (node (ref "3.3V") (pin "3") (pinfunction "OUTPUT_3") (pintype "passive"))
      (node (ref "ACC") (pin "3") (pinfunction "IO_VDD_3") (pintype "power_in"))
      (node (ref "ACC") (pin "7") (pinfunction "VDD_7") (pintype "power_in"))
      (node (ref "BOOT") (pin "1") (pinfunction "VDD_VREFH_1") (pintype "passive"))
      (node (ref "BPS") (pin "1") (pinfunction "VDD_1") (pintype "power_in"))
      (node (ref "BUZZER") (pin "2") (pinfunction "+POLARITY_2") (pintype "passive"))
      (node (ref "C104") (pin "2") (pinfunction "2_2") (pintype "passive"))
      (node (ref "C201") (pin "2") (pinfunction "2_2") (pintype "passive"))
      (node (ref "C202") (pin "2") (pinfunction "2_2") (pintype "passive"))
      (node (ref "C203") (pin "2") (pinfunction "2_2") (pintype "passive"))
      (node (ref "C204") (pin "2") (pinfunction "2_2") (pintype "passive"))
      (node (ref "C205") (pin "2") (pinfunction "2_2") (pintype "passive"))
      (node (ref "C209") (pin "2") (pinfunction "2_2") (pintype "passive"))
      (node (ref "C210") (pin "2") (pinfunction "2_2") (pintype "passive"))
      (node (ref "C301") (pin "2") (pinfunction "2_2") (pintype "passive"))
      (node (ref "C302") (pin "2") (pinfunction "2_2") (pintype "passive"))
      (node (ref "C401") (pin "2") (pinfunction "2_2") (pintype "passive"))
      (node (ref "C402") (pin "2") (pinfunction "2_2") (pintype "passive"))
      (node (ref "C403") (pin "2") (pinfunction "2_2") (pintype "passive"))
      (node (ref "C404") (pin "2") (pinfunction "2_2") (pintype "passive"))
      (node (ref "C405") (pin "2") (pinfunction "2_2") (pintype "passive"))
      (node (ref "C407") (pin "2") (pinfunction "2_2") (pintype "passive"))
      (node (ref "C509") (pin "1") (pinfunction "1_1") (pintype "passive"))
      (node (ref "C601") (pin "2") (pinfunction "2_2") (pintype "passive"))
      (node (ref "C602") (pin "2") (pinfunction "2_2") (pintype "passive"))
      (node (ref "C603") (pin "2") (pinfunction "2_2") (pintype "passive"))
      (node (ref "CAN0 TRAN") (pin "3") (pinfunction "VCC_3") (pintype "power_in"))
      (node (ref "FB2") (pin "2") (pinfunction "2_2") (pintype "passive"))
      (node (ref "GPS") (pin "17") (pinfunction "VCC_17") (pintype "power_in"))
      (node (ref "GPS") (pin "2") (pinfunction "VCC_IO_2") (pintype "power_in"))
      (node (ref "GPS") (pin "3") (pinfunction "V_BCKP_3") (pintype "power_in"))
      (node (ref "IMU1") (pin "28") (pinfunction "VDDIO_28") (pintype "power_in"))
      (node (ref "IMU1") (pin "3") (pinfunction "VDD_3") (pintype "power_in"))
      (node (ref "IMU2") (pin "11") (pinfunction "VDDIO_11") (pintype "power_in"))
      (node (ref "IMU2") (pin "3") (pinfunction "VDD_3") (pintype "power_in"))
      (node (ref "LoRa Misc") (pin "4") (pinfunction "4_4") (pintype "passive"))
      (node (ref "MCU") (pin "108") (pinfunction "VDD_108") (pintype "input"))
      (node (ref "MCU") (pin "122") (pinfunction "VDD_122") (pintype "input"))
      (node (ref "MCU") (pin "135") (pinfunction "VDD_135") (pintype "input"))
      (node (ref "MCU") (pin "16") (pinfunction "VDD_16") (pintype "input"))
      (node (ref "MCU") (pin "21") (pinfunction "VREG_OUT_21") (pintype "input"))
      (node (ref "MCU") (pin "42") (pinfunction "VBAT_42") (pintype "input"))
      (node (ref "MCU") (pin "43") (pinfunction "VDD_43") (pintype "input"))
      (node (ref "MCU") (pin "5") (pinfunction "VDD_5") (pintype "input"))
      (node (ref "MCU") (pin "56") (pinfunction "VDD_56") (pintype "input"))
      (node (ref "MCU") (pin "70") (pinfunction "VDD_70") (pintype "input"))
      (node (ref "MCU") (pin "94") (pinfunction "VDD_94") (pintype "input"))
      (node (ref "MUX") (pin "16") (pinfunction "VCC_16") (pintype "passive"))
      (node (ref "NRF Misc") (pin "4") (pinfunction "4_4") (pintype "passive"))
      (node (ref "R102") (pin "2") (pinfunction "2_2") (pintype "passive"))
      (node (ref "R104") (pin "1") (pinfunction "1_1") (pintype "passive"))
      (node (ref "R303") (pin "1") (pinfunction "1_1") (pintype "passive"))
      (node (ref "R304") (pin "2") (pinfunction "2_2") (pintype "passive"))
      (node (ref "R402") (pin "1") (pinfunction "1_1") (pintype "passive"))
      (node (ref "R403") (pin "1") (pinfunction "1_1") (pintype "passive"))
      (node (ref "R405") (pin "1") (pinfunction "1_1") (pintype "passive"))
      (node (ref "R406") (pin "2") (pinfunction "2_2") (pintype "passive"))
      (node (ref "R407") (pin "1") (pinfunction "1_1") (pintype "passive"))
      (node (ref "R408") (pin "1") (pinfunction "1_1") (pintype "passive"))
      (node (ref "R602") (pin "1") (pinfunction "1_1") (pintype "passive"))
      (node (ref "R603") (pin "1") (pinfunction "1_1") (pintype "passive"))
      (node (ref "RS-485") (pin "1") (pinfunction "VCC_1") (pintype "passive"))
      (node (ref "SD") (pin "4") (pinfunction "VDD_4") (pintype "passive"))
    )
    (net (code "174") (name "5V") (class "Default")
      (node (ref "5V") (pin "3") (pinfunction "OUTPUT_3") (pintype "passive"))
      (node (ref "C106") (pin "2") (pinfunction "2_2") (pintype "passive"))
      (node (ref "C604") (pin "2") (pinfunction "2_2") (pintype "passive"))
      (node (ref "R103") (pin "2") (pinfunction "2_2") (pintype "passive"))
      (node (ref "R106") (pin "1") (pinfunction "1_1") (pintype "passive"))
      (node (ref "Secondary Connector") (pin "14") (pinfunction "14_14") (pintype "passive"))
      (node (ref "Secondary Connector") (pin "16") (pinfunction "16_16") (pintype "passive"))
      (node (ref "Secondary Connector") (pin "17") (pinfunction "17_17") (pintype "passive"))
      (node (ref "Secondary Connector") (pin "19") (pinfunction "19_19") (pintype "passive"))
      (node (ref "Secondary Connector") (pin "20") (pinfunction "20_20") (pintype "passive"))
      (node (ref "Secondary Connector") (pin "22") (pinfunction "22_22") (pintype "passive"))
      (node (ref "Secondary Connector") (pin "23") (pinfunction "23_23") (pintype "passive"))
      (node (ref "Secondary Connector") (pin "25") (pinfunction "25_25") (pintype "passive"))
    )
    (net (code "175") (name "GND") (class "Default")
      (node (ref "3.3V") (pin "2") (pinfunction "ADJ/GND_1_2") (pintype "passive"))
      (node (ref "3.3V") (pin "4") (pinfunction "ADJ/GND_2_4") (pintype "passive"))
      (node (ref "5V") (pin "2") (pinfunction "ADJ/GND_1_2") (pintype "passive"))
      (node (ref "5V") (pin "4") (pinfunction "ADJ/GND_2_4") (pintype "passive"))
      (node (ref "ACC") (pin "8") (pinfunction "GND_8") (pintype "power_in"))
      (node (ref "ACC") (pin "9") (pinfunction "GND_9") (pintype "power_in"))
      (node (ref "BOOT") (pin "17") (pinfunction "EP_17") (pintype "passive"))
      (node (ref "BOOT") (pin "2") (pinfunction "VREFL_VSS_2") (pintype "passive"))
      (node (ref "BPS") (pin "2") (pinfunction "PS_2") (pintype "input"))
      (node (ref "BPS") (pin "3") (pinfunction "GND_3") (pintype "power_in"))
      (node (ref "BUCK") (pin "2") (pinfunction "GROUND_2") (pintype "passive"))
      (node (ref "Boot J") (pin "5") (pinfunction "5_5") (pintype "passive"))
      (node (ref "C101") (pin "2") (pinfunction "-_2") (pintype "passive"))
      (node (ref "C102") (pin "1") (pinfunction "1_1") (pintype "passive"))
      (node (ref "C103") (pin "1") (pinfunction "1_1") (pintype "passive"))
      (node (ref "C104") (pin "1") (pinfunction "1_1") (pintype "passive"))
      (node (ref "C105") (pin "1") (pinfunction "1_1") (pintype "passive"))
      (node (ref "C106") (pin "1") (pinfunction "1_1") (pintype "passive"))
      (node (ref "C201") (pin "1") (pinfunction "1_1") (pintype "passive"))
      (node (ref "C202") (pin "1") (pinfunction "1_1") (pintype "passive"))
      (node (ref "C203") (pin "1") (pinfunction "1_1") (pintype "passive"))
      (node (ref "C204") (pin "1") (pinfunction "1_1") (pintype "passive"))
      (node (ref "C205") (pin "1") (pinfunction "1_1") (pintype "passive"))
      (node (ref "C209") (pin "1") (pinfunction "1_1") (pintype "passive"))
      (node (ref "C210") (pin "1") (pinfunction "1_1") (pintype "passive"))
      (node (ref "C301") (pin "1") (pinfunction "1_1") (pintype "passive"))
      (node (ref "C302") (pin "1") (pinfunction "1_1") (pintype "passive"))
      (node (ref "C401") (pin "1") (pinfunction "1_1") (pintype "passive"))
      (node (ref "C402") (pin "1") (pinfunction "1_1") (pintype "passive"))
      (node (ref "C403") (pin "1") (pinfunction "1_1") (pintype "passive"))
      (node (ref "C404") (pin "1") (pinfunction "1_1") (pintype "passive"))
      (node (ref "C405") (pin "1") (pinfunction "1_1") (pintype "passive"))
      (node (ref "C406") (pin "1") (pinfunction "1_1") (pintype "passive"))
      (node (ref "C407") (pin "1") (pinfunction "1_1") (pintype "passive"))
      (node (ref "C509") (pin "2") (pinfunction "2_2") (pintype "passive"))
      (node (ref "C601") (pin "1") (pinfunction "1_1") (pintype "passive"))
      (node (ref "C602") (pin "1") (pinfunction "1_1") (pintype "passive"))
      (node (ref "C603") (pin "1") (pinfunction "1_1") (pintype "passive"))
      (node (ref "C604") (pin "1") (pinfunction "1_1") (pintype "passive"))
      (node (ref "CAN0 TRAN") (pin "2") (pinfunction "GND_2") (pintype "power_in"))
      (node (ref "DS1") (pin "1") (pinfunction "K_1") (pintype "passive"))
      (node (ref "DS2") (pin "1") (pinfunction "K_1") (pintype "passive"))
      (node (ref "DS3") (pin "1") (pinfunction "K_1") (pintype "passive"))
      (node (ref "DS4") (pin "1") (pinfunction "K_1") (pintype "passive"))
      (node (ref "FB3") (pin "1") (pinfunction "1_1") (pintype "passive"))
      (node (ref "GPS") (pin "1") (pinfunction "GND_1") (pintype "power_in"))
      (node (ref "GPS") (pin "10") (pinfunction "GND_10") (pintype "power_in"))
      (node (ref "GPS") (pin "11") (pinfunction "GND_11") (pintype "power_in"))
      (node (ref "GPS") (pin "15") (pinfunction "GND_15") (pintype "power_in"))
      (node (ref "GPS") (pin "16") (pinfunction "GND_16") (pintype "power_in"))
      (node (ref "GPS") (pin "20") (pinfunction "GND_20") (pintype "power_in"))
      (node (ref "GPS") (pin "4") (pinfunction "GND_4") (pintype "power_in"))
      (node (ref "GPS") (pin "5") (pinfunction "GND_5") (pintype "power_in"))
      (node (ref "GPS") (pin "6") (pinfunction "GND_6") (pintype "power_in"))
      (node (ref "IMU1") (pin "17") (pinfunction "COM3_17") (pintype "input"))
      (node (ref "IMU1") (pin "18") (pinfunction "COM2_18") (pintype "bidirectional"))
      (node (ref "IMU1") (pin "2") (pinfunction "GND_2") (pintype "power_in"))
      (node (ref "IMU1") (pin "25") (pinfunction "GNDIO_25") (pintype "power_in"))
      (node (ref "IMU1") (pin "5") (pinfunction "PS1_5") (pintype "input"))
      (node (ref "IMU1") (pin "6") (pinfunction "PS0_6") (pintype "input"))
      (node (ref "IMU2") (pin "2") (pinfunction "NC_2") (pintype "passive"))
      (node (ref "IMU2") (pin "4") (pinfunction "GNDA_4") (pintype "power_in"))
      (node (ref "IMU2") (pin "6") (pinfunction "GNDIO_6") (pintype "power_in"))
      (node (ref "IMU2") (pin "7") (pinfunction "PS_7") (pintype "input"))
      (node (ref "J1") (pin "2") (pinfunction "NEG_2") (pintype "passive"))
      (node (ref "LoRa Misc") (pin "3") (pinfunction "3_3") (pintype "passive"))
      (node (ref "MCU") (pin "107") (pinfunction "VSS_107") (pintype "input"))
      (node (ref "MCU") (pin "121") (pinfunction "VSS_121") (pintype "input"))
      (node (ref "MCU") (pin "134") (pinfunction "VSS_134") (pintype "input"))
      (node (ref "MCU") (pin "17") (pinfunction "VSS_17") (pintype "input"))
      (node (ref "MCU") (pin "18") (pinfunction "VSS_18") (pintype "input"))
      (node (ref "MCU") (pin "44") (pinfunction "VSS_44") (pintype "input"))
      (node (ref "MCU") (pin "57") (pinfunction "VSS_57") (pintype "input"))
      (node (ref "MCU") (pin "6") (pinfunction "VSS_6") (pintype "input"))
      (node (ref "MCU") (pin "71") (pinfunction "VSS_71") (pintype "input"))
      (node (ref "MCU") (pin "93") (pinfunction "VSS_93") (pintype "input"))
      (node (ref "MUX") (pin "17") (pinfunction "EP_17") (pintype "passive"))
      (node (ref "MUX") (pin "5") (pinfunction "A_5") (pintype "passive"))
      (node (ref "MUX") (pin "8") (pinfunction "GND_8") (pintype "passive"))
      (node (ref "NRF Misc") (pin "3") (pinfunction "3_3") (pintype "passive"))
      (node (ref "Primary Connector") (pin "23") (pinfunction "23_23") (pintype "passive"))
      (node (ref "Primary Connector") (pin "48") (pinfunction "48_48") (pintype "passive"))
      (node (ref "Q10") (pin "2") (pinfunction "S_2") (pintype "passive"))
      (node (ref "R105") (pin "2") (pinfunction "2_2") (pintype "passive"))
      (node (ref "R107") (pin "2") (pinfunction "2_2") (pintype "passive"))
      (node (ref "R307") (pin "2") (pinfunction "2_2") (pintype "passive"))
      (node (ref "RS-485") (pin "4") (pinfunction "GND_4") (pintype "passive"))
      (node (ref "SD") (pin "11") (pinfunction "SHLD1_11") (pintype "passive"))
      (node (ref "SD") (pin "12") (pinfunction "SHLD2_12") (pintype "passive"))
      (node (ref "SD") (pin "6") (pinfunction "VSS2_6") (pintype "passive"))
      (node (ref "Secondary Connector") (pin "11") (pinfunction "11_11") (pintype "passive"))
      (node (ref "Secondary Connector") (pin "15") (pinfunction "15_15") (pintype "passive"))
      (node (ref "Secondary Connector") (pin "18") (pinfunction "18_18") (pintype "passive"))
      (node (ref "Secondary Connector") (pin "2") (pinfunction "2_2") (pintype "passive"))
      (node (ref "Secondary Connector") (pin "21") (pinfunction "21_21") (pintype "passive"))
      (node (ref "Secondary Connector") (pin "24") (pinfunction "24_24") (pintype "passive"))
      (node (ref "Secondary Connector") (pin "5") (pinfunction "5_5") (pintype "passive"))
      (node (ref "Secondary Connector") (pin "8") (pinfunction "8_8") (pintype "passive"))
      (node (ref "USB") (pin "10") (pinfunction "SHLD5_10") (pintype "passive"))
      (node (ref "USB") (pin "11") (pinfunction "SHLD6_11") (pintype "passive"))
      (node (ref "USB") (pin "5") (pinfunction "GND_5") (pintype "passive"))
      (node (ref "USB") (pin "6") (pinfunction "SHLD1_6") (pintype "passive"))
      (node (ref "USB") (pin "7") (pinfunction "SHLD2_7") (pintype "passive"))
      (node (ref "USB") (pin "8") (pinfunction "SHLD3_8") (pintype "passive"))
      (node (ref "USB") (pin "9") (pinfunction "SHLD4_9") (pintype "passive"))
      (node (ref "Y1") (pin "2") (pinfunction "GND_2") (pintype "power_in"))
      (node (ref "Y1") (pin "4") (pinfunction "GND_4") (pintype "power_in"))
    )
    (net (code "176") (name "Net-(3.3V-INPUT)") (class "Default")
      (node (ref "3.3V") (pin "1") (pinfunction "INPUT_1") (pintype "passive"))
      (node (ref "5V") (pin "1") (pinfunction "INPUT_1") (pintype "passive"))
      (node (ref "C103") (pin "2") (pinfunction "2_2") (pintype "passive"))
      (node (ref "C105") (pin "2") (pinfunction "2_2") (pintype "passive"))
      (node (ref "D1") (pin "1") (pinfunction "C_1") (pintype "passive"))
    )
    (net (code "177") (name "Net-(BUCK-+VOUT)") (class "Default")
      (node (ref "BUCK") (pin "3") (pinfunction "+VOUT_3") (pintype "passive"))
      (node (ref "C102") (pin "2") (pinfunction "2_2") (pintype "passive"))
      (node (ref "D2") (pin "1") (pinfunction "C_1") (pintype "passive"))
      (node (ref "F1") (pin "1") (pinfunction "1_1") (pintype "passive"))
    )
    (net (code "178") (name "Net-(BUZZER--POLARITY)") (class "Default")
      (node (ref "BUZZER") (pin "3") (pinfunction "-POLARITY_3") (pintype "passive"))
      (node (ref "R601") (pin "2") (pinfunction "2_2") (pintype "passive"))
    )
    (net (code "179") (name "Net-(CAN0 TRAN-RS)") (class "Default")
      (node (ref "CAN0 TRAN") (pin "8") (pinfunction "RS_8") (pintype "input"))
      (node (ref "R307") (pin "1") (pinfunction "1_1") (pintype "passive"))
    )
    (net (code "180") (name "Net-(D1-A)") (class "Default")
      (node (ref "D1") (pin "2") (pinfunction "A_2") (pintype "passive"))
      (node (ref "FB1") (pin "2") (pinfunction "2_2") (pintype "passive"))
    )
    (net (code "181") (name "Net-(DS1-A)") (class "Default")
      (node (ref "DS1") (pin "2") (pinfunction "A_2") (pintype "passive"))
      (node (ref "R101") (pin "1") (pinfunction "1_1") (pintype "passive"))
    )
    (net (code "182") (name "Net-(DS2-A)") (class "Default")
      (node (ref "DS2") (pin "2") (pinfunction "A_2") (pintype "passive"))
      (node (ref "R102") (pin "1") (pinfunction "1_1") (pintype "passive"))
    )
    (net (code "183") (name "Net-(DS3-A)") (class "Default")
      (node (ref "DS3") (pin "2") (pinfunction "A_2") (pintype "passive"))
      (node (ref "R103") (pin "1") (pinfunction "1_1") (pintype "passive"))
    )
    (net (code "184") (name "Net-(DS4-A)") (class "Default")
      (node (ref "DS4") (pin "2") (pinfunction "A_2") (pintype "passive"))
      (node (ref "R401") (pin "2") (pinfunction "2_2") (pintype "passive"))
    )
    (net (code "185") (name "Net-(F1-Pad2)") (class "Default")
      (node (ref "F1") (pin "2") (pinfunction "2_2") (pintype "passive"))
      (node (ref "FB1") (pin "1") (pinfunction "1_1") (pintype "passive"))
    )
    (net (code "186") (name "Net-(GPS-EXTINT)") (class "Default")
      (node (ref "FB8") (pin "1") (pinfunction "1_1") (pintype "passive"))
      (node (ref "GPS") (pin "19") (pinfunction "EXTINT_19") (pintype "input"))
    )
    (net (code "187") (name "Net-(GPS-SCL)") (class "Default")
      (node (ref "FB6") (pin "2") (pinfunction "2_2") (pintype "passive"))
      (node (ref "GPS") (pin "12") (pinfunction "SCL_12") (pintype "input"))
    )
    (net (code "188") (name "Net-(GPS-SDA)") (class "Default")
      (node (ref "FB7") (pin "2") (pinfunction "2_2") (pintype "passive"))
      (node (ref "GPS") (pin "9") (pinfunction "SDA_9") (pintype "bidirectional"))
    )
    (net (code "189") (name "Net-(GPS-TIMEPULSE)") (class "Default")
      (node (ref "FB9") (pin "1") (pinfunction "1_1") (pintype "passive"))
      (node (ref "GPS") (pin "7") (pinfunction "TIMEPULSE_7") (pintype "output"))
    )
    (net (code "190") (name "Net-(GPS-~{RESET})") (class "Default")
      (node (ref "FB5") (pin "2") (pinfunction "2_2") (pintype "passive"))
      (node (ref "GPS") (pin "18") (pinfunction "~{RESET}_18") (pintype "input"))
    )
    (net (code "191") (name "Net-(IMU1-CAP)") (class "Default")
      (node (ref "C406") (pin "2") (pinfunction "2_2") (pintype "passive"))
      (node (ref "IMU1") (pin "9") (pinfunction "CAP_9") (pintype "passive"))
    )
    (net (code "192") (name "Net-(IMU1-~{BOOT_LOAD_PIN})") (class "Default")
      (node (ref "IMU1") (pin "4") (pinfunction "~{BOOT_LOAD_PIN}_4") (pintype "input"))
      (node (ref "R406") (pin "1") (pinfunction "1_1") (pintype "passive"))
    )
    (net (code "193") (name "Net-(Q10-D)") (class "Default")
      (node (ref "Q10") (pin "3") (pinfunction "D_3") (pintype "passive"))
      (node (ref "R601") (pin "1") (pinfunction "1_1") (pintype "passive"))
    )
    (net (code "194") (name "unconnected-(ACC-INT1-Pad5)") (class "Default")
      (node (ref "ACC") (pin "5") (pinfunction "INT1_5") (pintype "input+no_connect"))
    )
    (net (code "195") (name "unconnected-(ACC-INT2-Pad6)") (class "Default")
      (node (ref "ACC") (pin "6") (pinfunction "INT2_6") (pintype "input+no_connect"))
    )
    (net (code "196") (name "unconnected-(ACC-NC-Pad11)") (class "Default")
      (node (ref "ACC") (pin "11") (pinfunction "NC_11") (pintype "passive+no_connect"))
    )
    (net (code "197") (name "unconnected-(BOOT-PTA0{slash}IRQ_0-Pad14)") (class "Default")
      (node (ref "BOOT") (pin "14") (pinfunction "PTA0/IRQ_0_14") (pintype "passive+no_connect"))
    )
    (net (code "198") (name "unconnected-(BOOT-PTA1{slash}IRQ_1{slash}LPTMR0_ALT1-Pad15)") (class "Default")
      (node (ref "BOOT") (pin "15") (pinfunction "PTA1/IRQ_1/LPTMR0_ALT1_15") (pintype "passive+no_connect"))
    )
    (net (code "199") (name "unconnected-(BOOT-PTA2-Pad16)") (class "Default")
      (node (ref "BOOT") (pin "16") (pinfunction "PTA2_16") (pintype "passive+no_connect"))
    )
    (net (code "200") (name "unconnected-(BOOT-PTA5-Pad5)") (class "Default")
      (node (ref "BOOT") (pin "5") (pinfunction "PTA5_5") (pintype "passive+no_connect"))
    )
    (net (code "201") (name "unconnected-(BOOT-PTB3{slash}IRQ_10-Pad11)") (class "Default")
      (node (ref "BOOT") (pin "11") (pinfunction "PTB3/IRQ_10_11") (pintype "passive+no_connect"))
    )
    (net (code "202") (name "unconnected-(BOOT-PTB4{slash}IRQ_11-Pad12)") (class "Default")
      (node (ref "BOOT") (pin "12") (pinfunction "PTB4/IRQ_11_12") (pintype "passive+no_connect"))
    )
    (net (code "203") (name "unconnected-(BUZZER-NC-Pad1)") (class "Default")
      (node (ref "BUZZER") (pin "1") (pinfunction "NC_1") (pintype "passive+no_connect"))
    )
    (net (code "204") (name "unconnected-(BUZZER-NC-Pad4)") (class "Default")
      (node (ref "BUZZER") (pin "4") (pinfunction "NC_4") (pintype "passive+no_connect"))
    )
    (net (code "205") (name "unconnected-(CAN0 TRAN-VREF-Pad5)") (class "Default")
      (node (ref "CAN0 TRAN") (pin "5") (pinfunction "VREF_5") (pintype "output"))
    )
    (net (code "206") (name "unconnected-(GPS-RXD-Pad14)") (class "Default")
      (node (ref "GPS") (pin "14") (pinfunction "RXD_14") (pintype "input+no_connect"))
    )
    (net (code "207") (name "unconnected-(GPS-TXD-Pad13)") (class "Default")
      (node (ref "GPS") (pin "13") (pinfunction "TXD_13") (pintype "output+no_connect"))
    )
    (net (code "208") (name "unconnected-(GPS-~{SAFEBOOT}-Pad8)") (class "Default")
      (node (ref "GPS") (pin "8") (pinfunction "~{SAFEBOOT}_8") (pintype "input+no_connect"))
    )
    (net (code "209") (name "unconnected-(IMU1-BL_IND-Pad10)") (class "Default")
      (node (ref "IMU1") (pin "10") (pinfunction "BL_IND_10") (pintype "output+no_connect"))
    )
    (net (code "210") (name "unconnected-(IMU1-INT-Pad14)") (class "Default")
      (node (ref "IMU1") (pin "14") (pinfunction "INT_14") (pintype "passive+no_connect"))
    )
    (net (code "211") (name "unconnected-(IMU1-NC-Pad1)") (class "Default")
      (node (ref "IMU1") (pin "1") (pinfunction "NC_1") (pintype "passive+no_connect"))
    )
    (net (code "212") (name "unconnected-(IMU1-NC-Pad12)") (class "Default")
      (node (ref "IMU1") (pin "12") (pinfunction "NC_12") (pintype "passive+no_connect"))
    )
    (net (code "213") (name "unconnected-(IMU1-NC-Pad13)") (class "Default")
      (node (ref "IMU1") (pin "13") (pinfunction "NC_13") (pintype "passive+no_connect"))
    )
    (net (code "214") (name "unconnected-(IMU1-NC-Pad15)") (class "Default")
      (node (ref "IMU1") (pin "15") (pinfunction "NC_15") (pintype "passive+no_connect"))
    )
    (net (code "215") (name "unconnected-(IMU1-NC-Pad16)") (class "Default")
      (node (ref "IMU1") (pin "16") (pinfunction "NC_16") (pintype "passive+no_connect"))
    )
    (net (code "216") (name "unconnected-(IMU1-NC-Pad21)") (class "Default")
      (node (ref "IMU1") (pin "21") (pinfunction "NC_21") (pintype "passive+no_connect"))
    )
    (net (code "217") (name "unconnected-(IMU1-NC-Pad22)") (class "Default")
      (node (ref "IMU1") (pin "22") (pinfunction "NC_22") (pintype "passive+no_connect"))
    )
    (net (code "218") (name "unconnected-(IMU1-NC-Pad23)") (class "Default")
      (node (ref "IMU1") (pin "23") (pinfunction "NC_23") (pintype "passive+no_connect"))
    )
    (net (code "219") (name "unconnected-(IMU1-NC-Pad24)") (class "Default")
      (node (ref "IMU1") (pin "24") (pinfunction "NC_24") (pintype "passive+no_connect"))
    )
    (net (code "220") (name "unconnected-(IMU1-SWCLK-Pad8)") (class "Default")
      (node (ref "IMU1") (pin "8") (pinfunction "SWCLK_8") (pintype "input+no_connect"))
    )
    (net (code "221") (name "unconnected-(IMU1-SWDIO-Pad7)") (class "Default")
      (node (ref "IMU1") (pin "7") (pinfunction "SWDIO_7") (pintype "bidirectional+no_connect"))
    )
    (net (code "222") (name "unconnected-(IMU1-XIN32-Pad27)") (class "Default")
      (node (ref "IMU1") (pin "27") (pinfunction "XIN32_27") (pintype "input+no_connect"))
    )
    (net (code "223") (name "unconnected-(IMU1-XOUT32-Pad26)") (class "Default")
      (node (ref "IMU1") (pin "26") (pinfunction "XOUT32_26") (pintype "passive+no_connect"))
    )
    (net (code "224") (name "unconnected-(IMU2-INT1-Pad16)") (class "Default")
      (node (ref "IMU2") (pin "16") (pinfunction "INT1_16") (pintype "output+no_connect"))
    )
    (net (code "225") (name "unconnected-(IMU2-INT2-Pad1)") (class "Default")
      (node (ref "IMU2") (pin "1") (pinfunction "INT2_1") (pintype "output+no_connect"))
    )
    (net (code "226") (name "unconnected-(IMU2-INT3-Pad12)") (class "Default")
      (node (ref "IMU2") (pin "12") (pinfunction "INT3_12") (pintype "output+no_connect"))
    )
    (net (code "227") (name "unconnected-(IMU2-INT4-Pad13)") (class "Default")
      (node (ref "IMU2") (pin "13") (pinfunction "INT4_13") (pintype "output+no_connect"))
    )
    (net (code "228") (name "unconnected-(MCU-ADC0_DM0{slash}ADC1_DM3-Pad28)") (class "Default")
      (node (ref "MCU") (pin "28") (pinfunction "ADC0_DM0/ADC1_DM3_28") (pintype "input+no_connect"))
    )
    (net (code "229") (name "unconnected-(MCU-ADC0_SE16{slash}CMP1_IN2{slash}ADC0_SE21-Pad36)") (class "Default")
      (node (ref "MCU") (pin "36") (pinfunction "ADC0_SE16/CMP1_IN2/ADC0_SE21_36") (pintype "input+no_connect"))
    )
    (net (code "230") (name "unconnected-(MCU-ADC1_SE16{slash}CMP2_IN2{slash}ADC0_SE22-Pad35)") (class "Default")
      (node (ref "MCU") (pin "35") (pinfunction "ADC1_SE16/CMP2_IN2/ADC0_SE22_35") (pintype "input+no_connect"))
    )
    (net (code "231") (name "unconnected-(MCU-PTB1-Pad82)") (class "Default")
      (node (ref "MCU") (pin "82") (pinfunction "PTB1_82") (pintype "input+no_connect"))
    )
    (net (code "232") (name "unconnected-(MCU-PTB16-Pad95)") (class "Default")
      (node (ref "MCU") (pin "95") (pinfunction "PTB16_95") (pintype "input+no_connect"))
    )
    (net (code "233") (name "unconnected-(MCU-PTB17-Pad96)") (class "Default")
      (node (ref "MCU") (pin "96") (pinfunction "PTB17_96") (pintype "input+no_connect"))
    )
    (net (code "234") (name "unconnected-(MCU-PTE9{slash}LLWU_P17-Pad12)") (class "Default")
      (node (ref "MCU") (pin "12") (pinfunction "PTE9/LLWU_P17_12") (pintype "input+no_connect"))
    )
    (net (code "235") (name "unconnected-(MCU-PTE12-Pad15)") (class "Default")
      (node (ref "MCU") (pin "15") (pinfunction "PTE12_15") (pintype "input+no_connect"))
    )
    (net (code "236") (name "unconnected-(MCU-USB1_DM-Pad26)") (class "Default")
      (node (ref "MCU") (pin "26") (pinfunction "USB1_DM_26") (pintype "input+no_connect"))
    )
    (net (code "237") (name "unconnected-(MCU-USB1_DP-Pad25)") (class "Default")
      (node (ref "MCU") (pin "25") (pinfunction "USB1_DP_25") (pintype "input+no_connect"))
    )
    (net (code "238") (name "unconnected-(MCU-USB1_VBUS-Pad27)") (class "Default")
      (node (ref "MCU") (pin "27") (pinfunction "USB1_VBUS_27") (pintype "input+no_connect"))
    )
    (net (code "239") (name "unconnected-(MCU-USB1_VSS-Pad24)") (class "Default")
      (node (ref "MCU") (pin "24") (pinfunction "USB1_VSS_24") (pintype "input+no_connect"))
    )
    (net (code "240") (name "unconnected-(MCU-VREG_IN0-Pad22)") (class "Default")
      (node (ref "MCU") (pin "22") (pinfunction "VREG_IN0_22") (pintype "input+no_connect"))
    )
    (net (code "241") (name "unconnected-(MCU-VREG_IN1-Pad23)") (class "Default")
      (node (ref "MCU") (pin "23") (pinfunction "VREG_IN1_23") (pintype "input+no_connect"))
    )
    (net (code "242") (name "unconnected-(MUX-NC-Pad6)") (class "Default")
      (node (ref "MUX") (pin "6") (pinfunction "NC_6") (pintype "passive+no_connect"))
    )
    (net (code "243") (name "unconnected-(SD-CD_A-Pad9)") (class "Default")
      (node (ref "SD") (pin "9") (pinfunction "CD_A_9") (pintype "passive+no_connect"))
    )
    (net (code "244") (name "unconnected-(SD-CD_B-Pad10)") (class "Default")
      (node (ref "SD") (pin "10") (pinfunction "CD_B_10") (pintype "passive+no_connect"))
    )
    (net (code "245") (name "unconnected-(USB-ID-Pad4)") (class "Default")
      (node (ref "USB") (pin "4") (pinfunction "ID_4") (pintype "passive+no_connect"))
    )
  )
)
